# PCB_Project_TrafficLight.net
KiCad netlist of a schematic drawn in Altium Designer
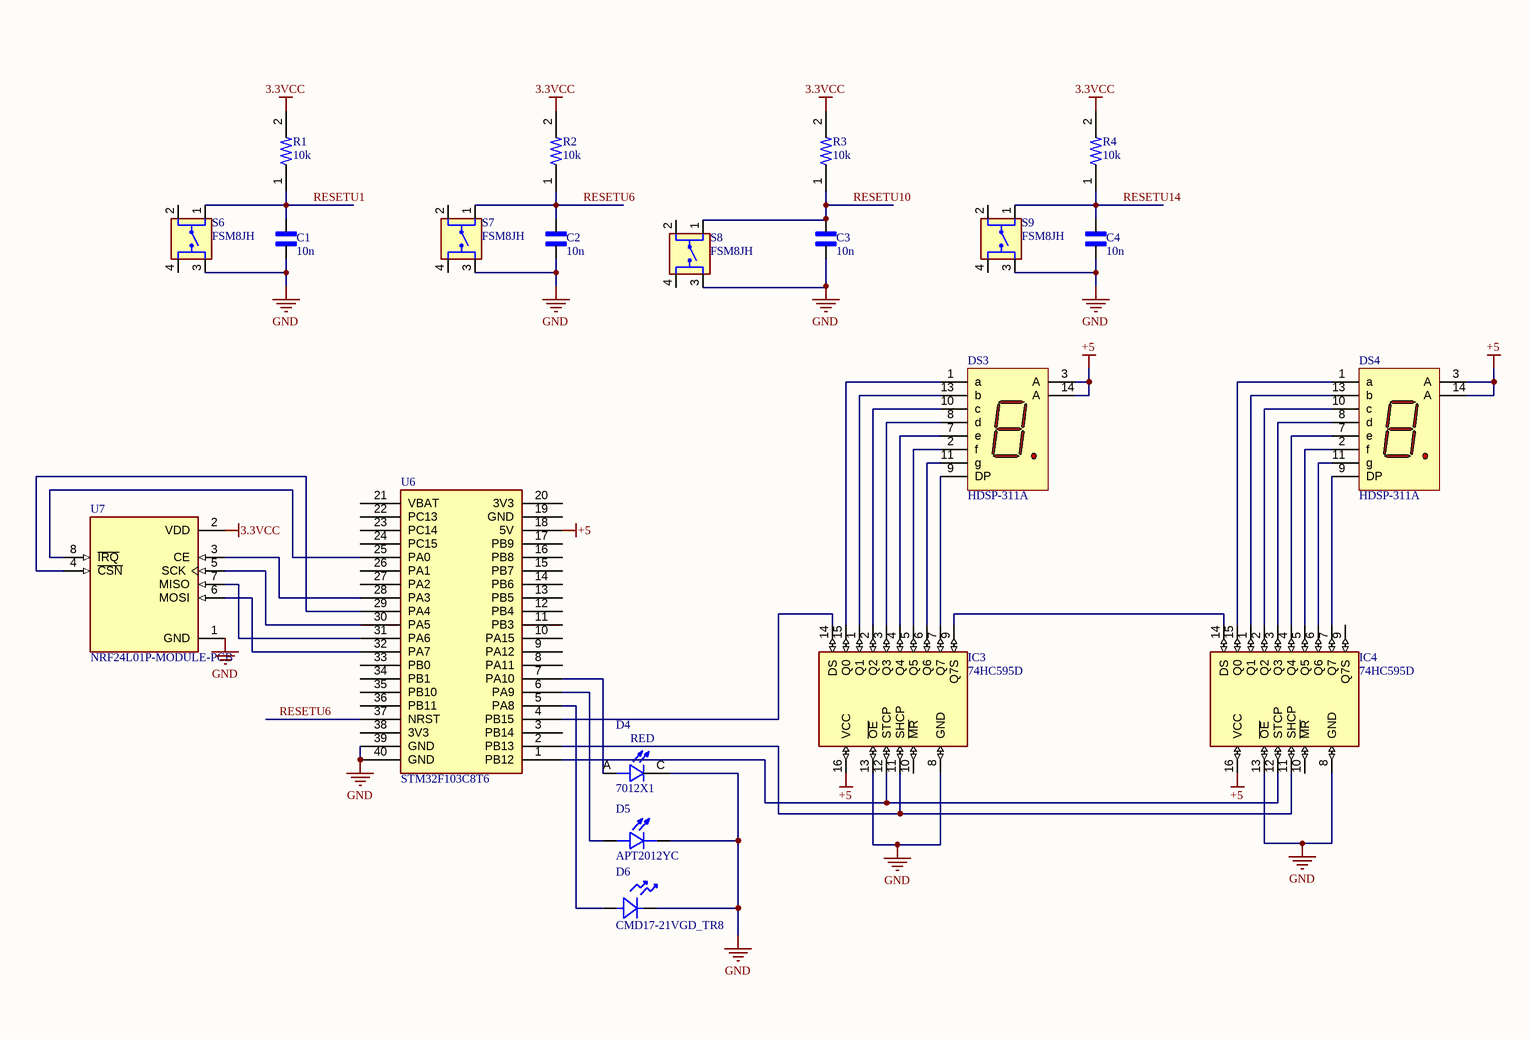
[diagram p0: PCB_Project_TrafficLight.SchDoc, left]
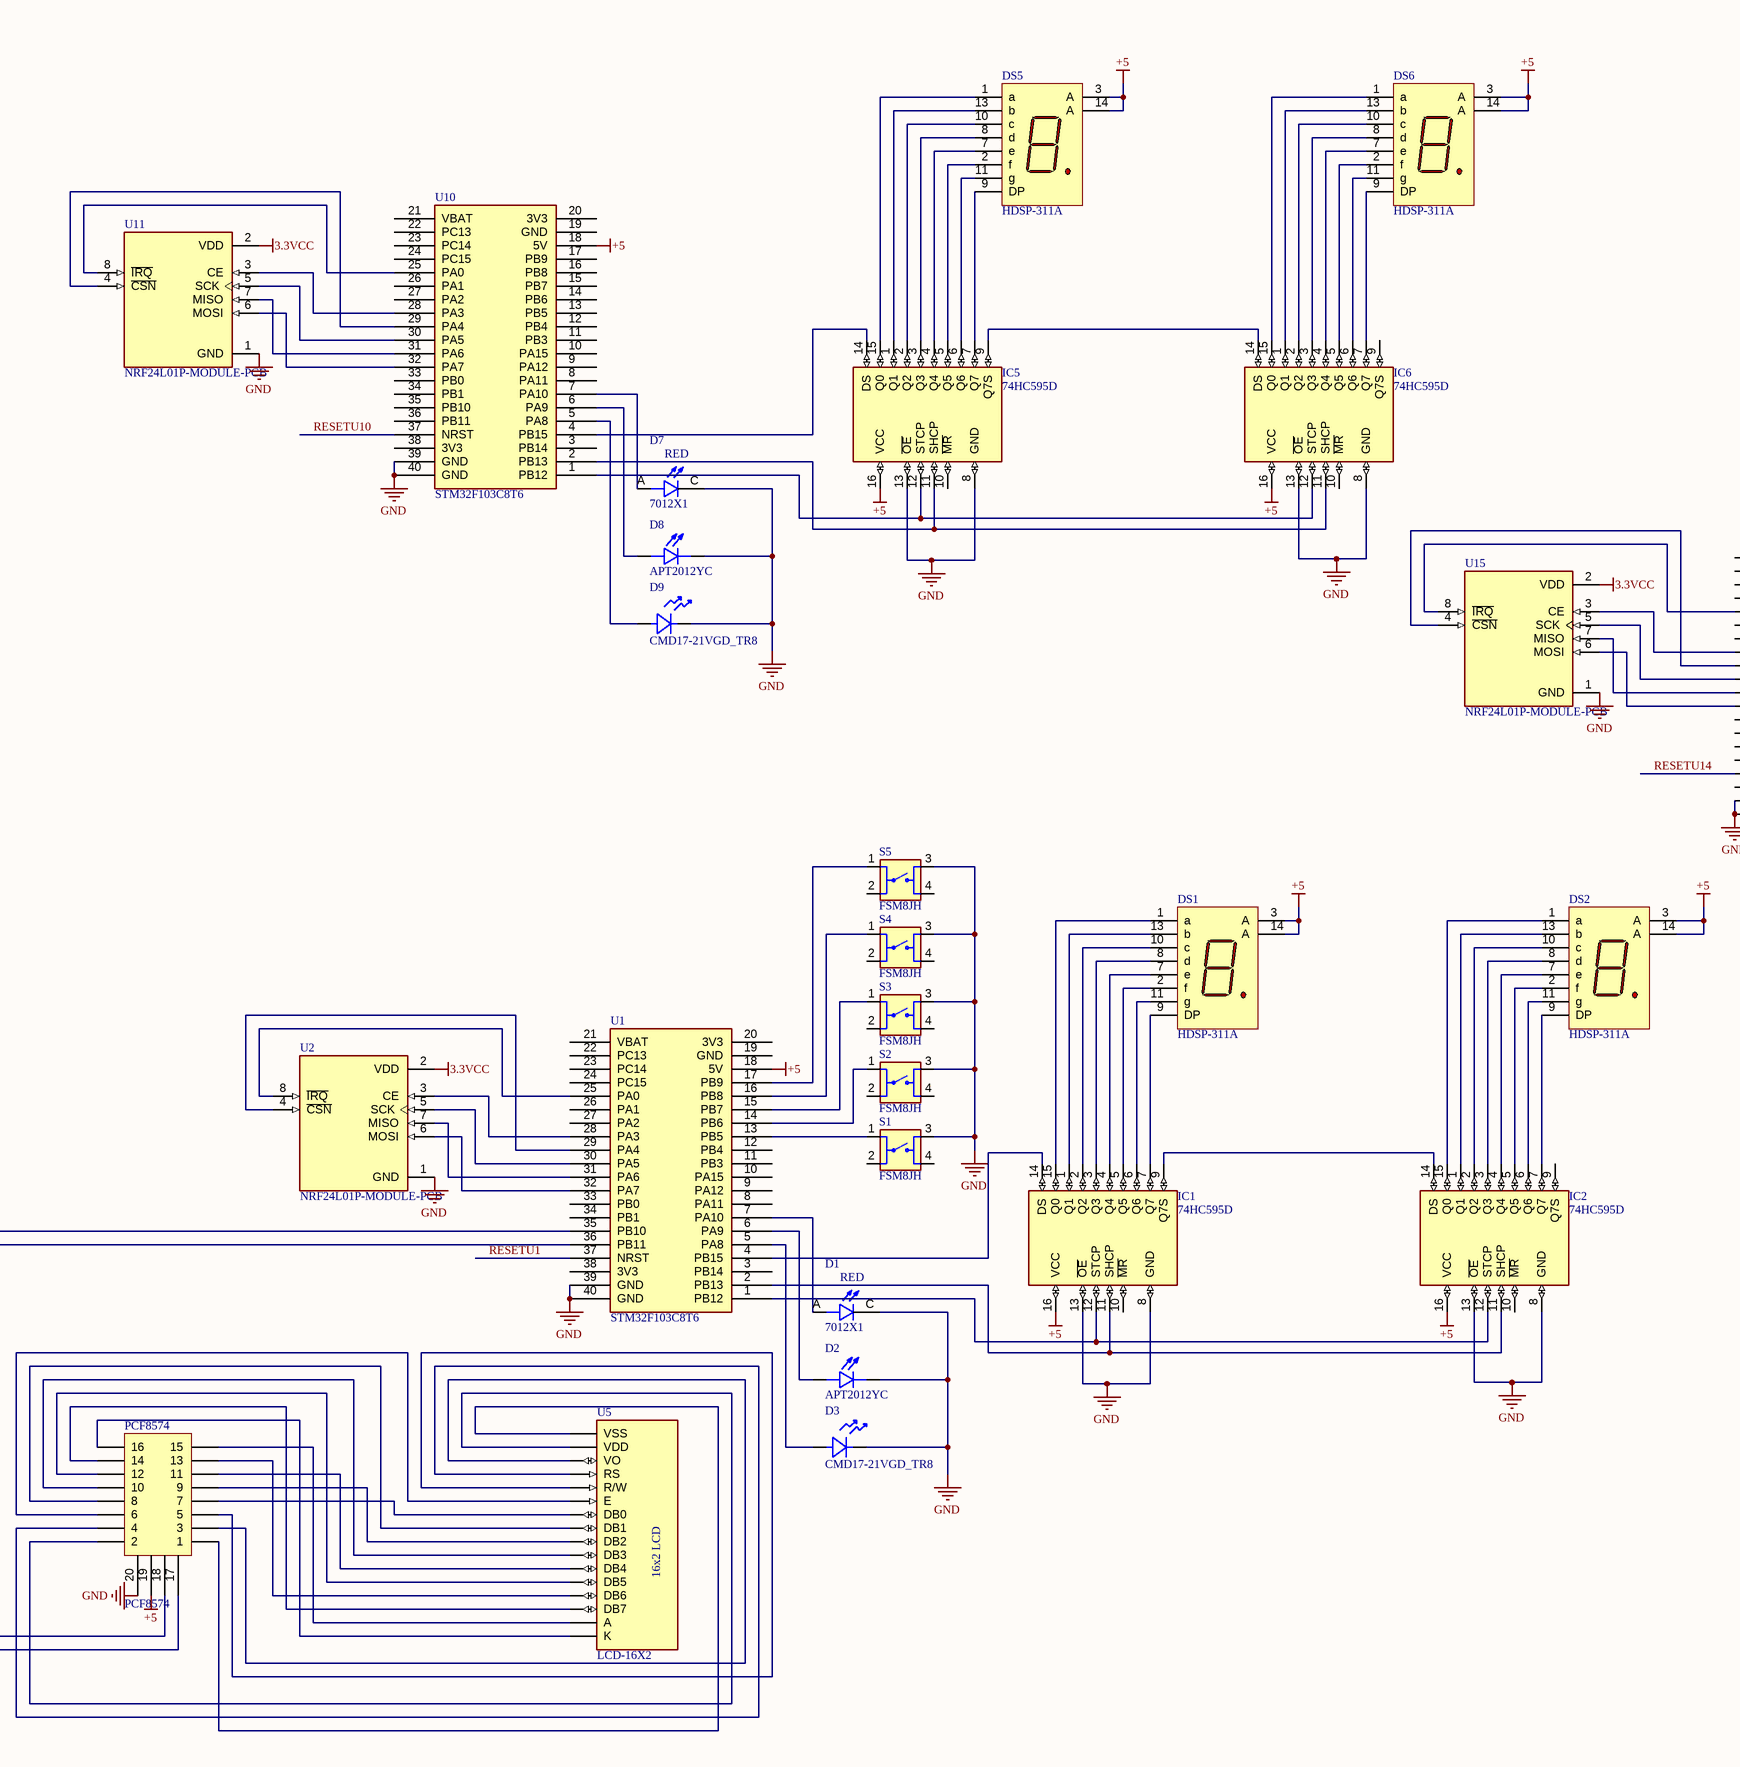
[diagram p1: PCB_Project_TrafficLight.SchDoc, middle]
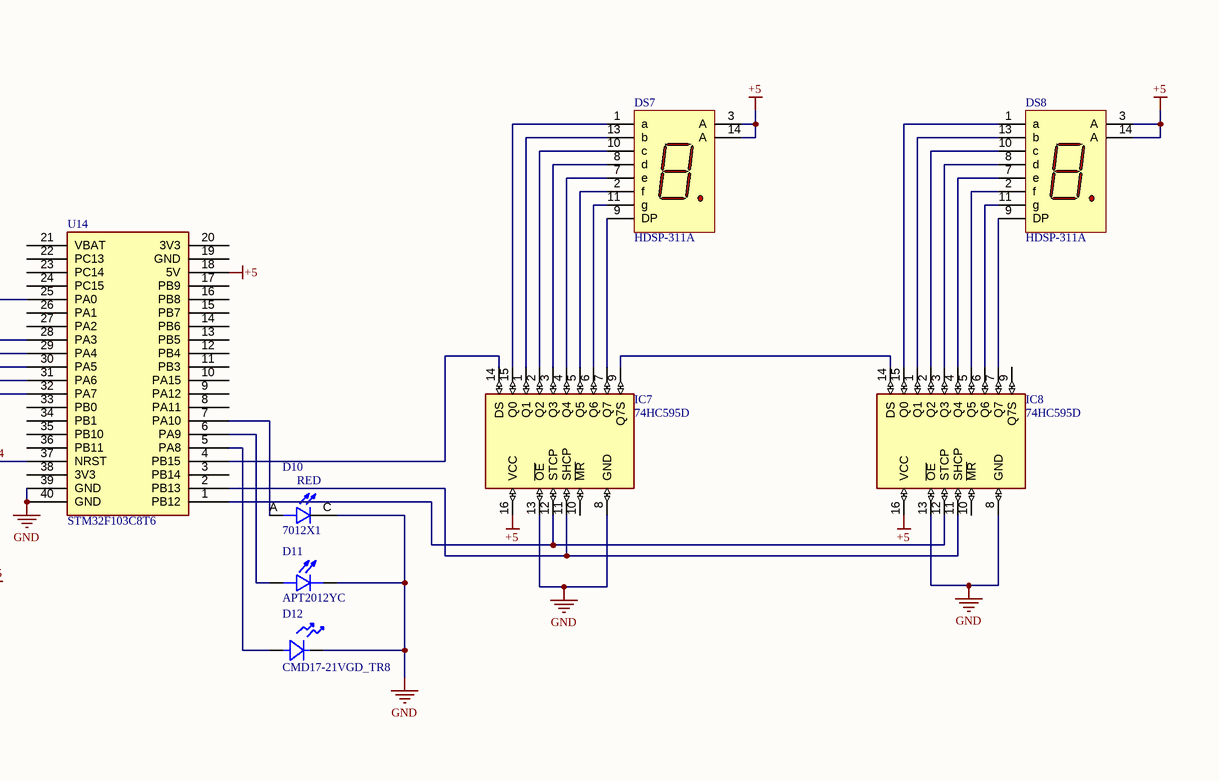
[diagram p2: PCB_Project_TrafficLight.SchDoc, right]

(export (version "E")
  (design (tool "Eeschema 10.0.6"))
  (components
    (comp (ref "C1")
      (value "10n")
      (footprint "CAPC1005X55N")
      (description "Multilayer Ceramic Capacitors MLCC - SMD/SMT")
      (fields (field (name "MF") "Murata") (field (name "MP") "GCM155R11H103KA40D"))
      (libsource (lib "GCM155R11H103KA40D") (part "GCM155R11H103KA40D"))
    )
    (comp (ref "C2")
      (value "10n")
      (footprint "CAPC1005X55N")
      (description "Multilayer Ceramic Capacitors MLCC - SMD/SMT")
      (fields (field (name "MF") "Murata") (field (name "MP") "GCM155R11H103KA40D"))
      (libsource (lib "GCM155R11H103KA40D") (part "GCM155R11H103KA40D"))
    )
    (comp (ref "C3")
      (value "10n")
      (footprint "CAPC1005X55N")
      (description "Multilayer Ceramic Capacitors MLCC - SMD/SMT")
      (fields (field (name "MF") "Murata") (field (name "MP") "GCM155R11H103KA40D"))
      (libsource (lib "GCM155R11H103KA40D") (part "GCM155R11H103KA40D"))
    )
    (comp (ref "C4")
      (value "10n")
      (footprint "CAPC1005X55N")
      (description "Multilayer Ceramic Capacitors MLCC - SMD/SMT")
      (fields (field (name "MF") "Murata") (field (name "MP") "GCM155R11H103KA40D"))
      (libsource (lib "GCM155R11H103KA40D") (part "GCM155R11H103KA40D"))
    )
    (comp (ref "D1")
      (value "7012X1")
      (footprint "LED_7012X1")
      (description "Red - LED Indication - Discrete 1.7V 0805 (2012 Metric)")
      (fields (field (name "MF") "VCC"))
      (libsource (lib "7012X1") (part "7012X1"))
    )
    (comp (ref "D2")
      (value "APT2012YC")
      (footprint "LED_APT2012YC")
      (fields (field (name "MF") "{'manufacturer': u'Kingbright'}"))
      (libsource (lib "APT2012YC") (part "APT2012YC"))
    )
    (comp (ref "D3")
      (value "CMD17-21VGD_TR8")
      (footprint "LED_CMD17-21VGD_TR8")
      (description "Green - LED Indication - Discrete 2.1V 0805 (2012 Metric)")
      (fields (field (name "MF") "VCC") (field (name "MP") "CMD17-21VGD/TR8"))
      (libsource (lib "CMD17-21VGD_TR8") (part "CMD17-21VGD_TR8"))
    )
    (comp (ref "D4")
      (value "7012X1")
      (footprint "LED_7012X1")
      (description "Red - LED Indication - Discrete 1.7V 0805 (2012 Metric)")
      (fields (field (name "MF") "VCC"))
      (libsource (lib "7012X1") (part "7012X1"))
    )
    (comp (ref "D5")
      (value "APT2012YC")
      (footprint "LED_APT2012YC")
      (fields (field (name "MF") "{'manufacturer': u'Kingbright'}"))
      (libsource (lib "APT2012YC") (part "APT2012YC"))
    )
    (comp (ref "D6")
      (value "CMD17-21VGD_TR8")
      (footprint "LED_CMD17-21VGD_TR8")
      (description "Green - LED Indication - Discrete 2.1V 0805 (2012 Metric)")
      (fields (field (name "MF") "VCC") (field (name "MP") "CMD17-21VGD/TR8"))
      (libsource (lib "CMD17-21VGD_TR8") (part "CMD17-21VGD_TR8"))
    )
    (comp (ref "D7")
      (value "7012X1")
      (footprint "LED_7012X1")
      (description "Red - LED Indication - Discrete 1.7V 0805 (2012 Metric)")
      (fields (field (name "MF") "VCC"))
      (libsource (lib "7012X1") (part "7012X1"))
    )
    (comp (ref "D8")
      (value "APT2012YC")
      (footprint "LED_APT2012YC")
      (fields (field (name "MF") "{'manufacturer': u'Kingbright'}"))
      (libsource (lib "APT2012YC") (part "APT2012YC"))
    )
    (comp (ref "D9")
      (value "CMD17-21VGD_TR8")
      (footprint "LED_CMD17-21VGD_TR8")
      (description "Green - LED Indication - Discrete 2.1V 0805 (2012 Metric)")
      (fields (field (name "MF") "VCC") (field (name "MP") "CMD17-21VGD/TR8"))
      (libsource (lib "CMD17-21VGD_TR8") (part "CMD17-21VGD_TR8"))
    )
    (comp (ref "D10")
      (value "7012X1")
      (footprint "LED_7012X1")
      (description "Red - LED Indication - Discrete 1.7V 0805 (2012 Metric)")
      (fields (field (name "MF") "VCC"))
      (libsource (lib "7012X1") (part "7012X1"))
    )
    (comp (ref "D11")
      (value "APT2012YC")
      (footprint "LED_APT2012YC")
      (fields (field (name "MF") "{'manufacturer': u'Kingbright'}"))
      (libsource (lib "APT2012YC") (part "APT2012YC"))
    )
    (comp (ref "D12")
      (value "CMD17-21VGD_TR8")
      (footprint "LED_CMD17-21VGD_TR8")
      (description "Green - LED Indication - Discrete 2.1V 0805 (2012 Metric)")
      (fields (field (name "MF") "VCC") (field (name "MP") "CMD17-21VGD/TR8"))
      (libsource (lib "CMD17-21VGD_TR8") (part "CMD17-21VGD_TR8"))
    )
    (comp (ref "DS1")
      (value "HDSP-311A")
      (footprint "F-10(14)")
      (description "10.16 mm Single Digit General Purpose AlGaAs Red 7-Segment Display: CA, RH DP")
      (fields (field (name "PUBLISHER") "Altium Limited"))
      (libsource (lib "Agilent LED Display 7-Segment, 1-Digit") (part "HDSP-311A"))
    )
    (comp (ref "DS2")
      (value "HDSP-311A")
      (footprint "F-10(14)")
      (description "10.16 mm Single Digit General Purpose AlGaAs Red 7-Segment Display: CA, RH DP")
      (fields (field (name "PUBLISHER") "Altium Limited"))
      (libsource (lib "Agilent LED Display 7-Segment, 1-Digit") (part "HDSP-311A"))
    )
    (comp (ref "DS3")
      (value "HDSP-311A")
      (footprint "F-10(14)")
      (description "10.16 mm Single Digit General Purpose AlGaAs Red 7-Segment Display: CA, RH DP")
      (fields (field (name "PUBLISHER") "Altium Limited"))
      (libsource (lib "Agilent LED Display 7-Segment, 1-Digit") (part "HDSP-311A"))
    )
    (comp (ref "DS4")
      (value "HDSP-311A")
      (footprint "F-10(14)")
      (description "10.16 mm Single Digit General Purpose AlGaAs Red 7-Segment Display: CA, RH DP")
      (fields (field (name "PUBLISHER") "Altium Limited"))
      (libsource (lib "Agilent LED Display 7-Segment, 1-Digit") (part "HDSP-311A"))
    )
    (comp (ref "DS5")
      (value "HDSP-311A")
      (footprint "F-10(14)")
      (description "10.16 mm Single Digit General Purpose AlGaAs Red 7-Segment Display: CA, RH DP")
      (fields (field (name "PUBLISHER") "Altium Limited"))
      (libsource (lib "Agilent LED Display 7-Segment, 1-Digit") (part "HDSP-311A"))
    )
    (comp (ref "DS6")
      (value "HDSP-311A")
      (footprint "F-10(14)")
      (description "10.16 mm Single Digit General Purpose AlGaAs Red 7-Segment Display: CA, RH DP")
      (fields (field (name "PUBLISHER") "Altium Limited"))
      (libsource (lib "Agilent LED Display 7-Segment, 1-Digit") (part "HDSP-311A"))
    )
    (comp (ref "DS7")
      (value "HDSP-311A")
      (footprint "F-10(14)")
      (description "10.16 mm Single Digit General Purpose AlGaAs Red 7-Segment Display: CA, RH DP")
      (fields (field (name "PUBLISHER") "Altium Limited"))
      (libsource (lib "Agilent LED Display 7-Segment, 1-Digit") (part "HDSP-311A"))
    )
    (comp (ref "DS8")
      (value "HDSP-311A")
      (footprint "F-10(14)")
      (description "10.16 mm Single Digit General Purpose AlGaAs Red 7-Segment Display: CA, RH DP")
      (fields (field (name "PUBLISHER") "Altium Limited"))
      (libsource (lib "Agilent LED Display 7-Segment, 1-Digit") (part "HDSP-311A"))
    )
    (comp (ref "IC1")
      (value "74HC595D")
      (footprint "SOIC127P600X175-16N")
      (description "Shift Register Single 8-Bit Serial to Serial/Parallel 16-Pin SOIC T/R")
      (fields (field (name "MF") "NXP Semiconductors"))
      (libsource (lib "74HC595D") (part "74HC595D"))
    )
    (comp (ref "IC2")
      (value "74HC595D")
      (footprint "SOIC127P600X175-16N")
      (description "Shift Register Single 8-Bit Serial to Serial/Parallel 16-Pin SOIC T/R")
      (fields (field (name "MF") "NXP Semiconductors"))
      (libsource (lib "74HC595D") (part "74HC595D"))
    )
    (comp (ref "IC3")
      (value "74HC595D")
      (footprint "SOIC127P600X175-16N")
      (description "Shift Register Single 8-Bit Serial to Serial/Parallel 16-Pin SOIC T/R")
      (fields (field (name "MF") "NXP Semiconductors"))
      (libsource (lib "74HC595D") (part "74HC595D"))
    )
    (comp (ref "IC4")
      (value "74HC595D")
      (footprint "SOIC127P600X175-16N")
      (description "Shift Register Single 8-Bit Serial to Serial/Parallel 16-Pin SOIC T/R")
      (fields (field (name "MF") "NXP Semiconductors"))
      (libsource (lib "74HC595D") (part "74HC595D"))
    )
    (comp (ref "IC5")
      (value "74HC595D")
      (footprint "SOIC127P600X175-16N")
      (description "Shift Register Single 8-Bit Serial to Serial/Parallel 16-Pin SOIC T/R")
      (fields (field (name "MF") "NXP Semiconductors"))
      (libsource (lib "74HC595D") (part "74HC595D"))
    )
    (comp (ref "IC6")
      (value "74HC595D")
      (footprint "SOIC127P600X175-16N")
      (description "Shift Register Single 8-Bit Serial to Serial/Parallel 16-Pin SOIC T/R")
      (fields (field (name "MF") "NXP Semiconductors"))
      (libsource (lib "74HC595D") (part "74HC595D"))
    )
    (comp (ref "IC7")
      (value "74HC595D")
      (footprint "SOIC127P600X175-16N")
      (description "Shift Register Single 8-Bit Serial to Serial/Parallel 16-Pin SOIC T/R")
      (fields (field (name "MF") "NXP Semiconductors"))
      (libsource (lib "74HC595D") (part "74HC595D"))
    )
    (comp (ref "IC8")
      (value "74HC595D")
      (footprint "SOIC127P600X175-16N")
      (description "Shift Register Single 8-Bit Serial to Serial/Parallel 16-Pin SOIC T/R")
      (fields (field (name "MF") "NXP Semiconductors"))
      (libsource (lib "74HC595D") (part "74HC595D"))
    )
    (comp (ref "PCF8574")
      (value "PCF8574")
      (footprint "PCF8574")
      (libsource (lib "PCF8574") (part "PCF8574"))
    )
    (comp (ref "R1")
      (value "10k")
      (footprint "RESC1608X50N_CPF0603F10KC1")
      (description "Res Thin Film 0603 10K Ohm 1% 1/16W Â±50ppm/Â°C Molded SMD SMD Paper T/R")
      (fields (field (name "TOLERANCE") "1%") (field (name "MF") "TE Connectivity"))
      (libsource (lib "CPF0603F10KC1") (part "CPF0603F10KC1"))
    )
    (comp (ref "R2")
      (value "10k")
      (footprint "RESC1608X50N_CPF0603F10KC1")
      (description "Res Thin Film 0603 10K Ohm 1% 1/16W Â±50ppm/Â°C Molded SMD SMD Paper T/R")
      (fields (field (name "TOLERANCE") "1%") (field (name "MF") "TE Connectivity"))
      (libsource (lib "CPF0603F10KC1") (part "CPF0603F10KC1"))
    )
    (comp (ref "R3")
      (value "10k")
      (footprint "RESC1608X50N_CPF0603F10KC1")
      (description "Res Thin Film 0603 10K Ohm 1% 1/16W Â±50ppm/Â°C Molded SMD SMD Paper T/R")
      (fields (field (name "TOLERANCE") "1%") (field (name "MF") "TE Connectivity"))
      (libsource (lib "CPF0603F10KC1") (part "CPF0603F10KC1"))
    )
    (comp (ref "R4")
      (value "10k")
      (footprint "RESC1608X50N_CPF0603F10KC1")
      (description "Res Thin Film 0603 10K Ohm 1% 1/16W Â±50ppm/Â°C Molded SMD SMD Paper T/R")
      (fields (field (name "TOLERANCE") "1%") (field (name "MF") "TE Connectivity"))
      (libsource (lib "CPF0603F10KC1") (part "CPF0603F10KC1"))
    )
    (comp (ref "S1")
      (value "FSM8JH")
      (footprint "SW_FSM8JH")
      (description "Tactile Switch SPST-NO Top Actuated Through Hole")
      (fields (field (name "MF") "TE Connectivity"))
      (libsource (lib "") (part "FSM8JH_1"))
    )
    (comp (ref "S2")
      (value "FSM8JH")
      (footprint "SW_FSM8JH")
      (description "Tactile Switch SPST-NO Top Actuated Through Hole")
      (fields (field (name "MF") "TE Connectivity"))
      (libsource (lib "") (part "FSM8JH_1"))
    )
    (comp (ref "S3")
      (value "FSM8JH")
      (footprint "SW_FSM8JH")
      (description "Tactile Switch SPST-NO Top Actuated Through Hole")
      (fields (field (name "MF") "TE Connectivity"))
      (libsource (lib "") (part "FSM8JH_1"))
    )
    (comp (ref "S4")
      (value "FSM8JH")
      (footprint "SW_FSM8JH")
      (description "Tactile Switch SPST-NO Top Actuated Through Hole")
      (fields (field (name "MF") "TE Connectivity"))
      (libsource (lib "") (part "FSM8JH_1"))
    )
    (comp (ref "S5")
      (value "FSM8JH")
      (footprint "SW_FSM8JH")
      (description "Tactile Switch SPST-NO Top Actuated Through Hole")
      (fields (field (name "MF") "TE Connectivity"))
      (libsource (lib "") (part "FSM8JH_1"))
    )
    (comp (ref "S6")
      (value "FSM8JH")
      (footprint "SW_FSM8JH")
      (description "Tactile Switch SPST-NO Top Actuated Through Hole")
      (fields (field (name "MF") "TE Connectivity"))
      (libsource (lib "FSM8JH") (part "FSM8JH"))
    )
    (comp (ref "S7")
      (value "FSM8JH")
      (footprint "SW_FSM8JH")
      (description "Tactile Switch SPST-NO Top Actuated Through Hole")
      (fields (field (name "MF") "TE Connectivity"))
      (libsource (lib "FSM8JH") (part "FSM8JH"))
    )
    (comp (ref "S8")
      (value "FSM8JH")
      (footprint "SW_FSM8JH")
      (description "Tactile Switch SPST-NO Top Actuated Through Hole")
      (fields (field (name "MF") "TE Connectivity"))
      (libsource (lib "FSM8JH") (part "FSM8JH"))
    )
    (comp (ref "S9")
      (value "FSM8JH")
      (footprint "SW_FSM8JH")
      (description "Tactile Switch SPST-NO Top Actuated Through Hole")
      (fields (field (name "MF") "TE Connectivity"))
      (libsource (lib "FSM8JH") (part "FSM8JH"))
    )
    (comp (ref "U1")
      (value "STM32F103C8T6")
      (footprint "Stm32 BluePill")
      (description "Designed By @Alixahedi")
      (libsource (lib "Stm32 Blue Pill") (part "BluePill"))
    )
    (comp (ref "U2")
      (value "NRF24L01P-MODULE-PCB")
      (footprint "XCVR_NRF24L01P-MODULE-PCB")
      (description "- Transceiver For Use With nRF24L01+")
      (fields (field (name "MF") "Nordic Semiconductor"))
      (libsource (lib "NRF24L01P-MODULE-PCB") (part "NRF24L01P-MODULE-PCB"))
    )
    (comp (ref "U5")
      (value "LCD-16X2")
      (footprint "MODULE_LCD-16X2")
      (description "Display Development Tools 16x2 Black on Green Char LCD w Backlight")
      (fields (field (name "MF") "Gravitech"))
      (libsource (lib "LCD-16X2") (part "LCD-16X2"))
    )
    (comp (ref "U6")
      (value "STM32F103C8T6")
      (footprint "Stm32 BluePill")
      (description "Designed By @Alixahedi")
      (libsource (lib "Stm32 Blue Pill") (part "BluePill"))
    )
    (comp (ref "U7")
      (value "NRF24L01P-MODULE-PCB")
      (footprint "XCVR_NRF24L01P-MODULE-PCB")
      (description "- Transceiver For Use With nRF24L01+")
      (fields (field (name "MF") "Nordic Semiconductor"))
      (libsource (lib "NRF24L01P-MODULE-PCB") (part "NRF24L01P-MODULE-PCB"))
    )
    (comp (ref "U10")
      (value "STM32F103C8T6")
      (footprint "Stm32 BluePill")
      (description "Designed By @Alixahedi")
      (libsource (lib "Stm32 Blue Pill") (part "BluePill"))
    )
    (comp (ref "U11")
      (value "NRF24L01P-MODULE-PCB")
      (footprint "XCVR_NRF24L01P-MODULE-PCB")
      (description "- Transceiver For Use With nRF24L01+")
      (fields (field (name "MF") "Nordic Semiconductor"))
      (libsource (lib "NRF24L01P-MODULE-PCB") (part "NRF24L01P-MODULE-PCB"))
    )
    (comp (ref "U14")
      (value "STM32F103C8T6")
      (footprint "Stm32 BluePill")
      (description "Designed By @Alixahedi")
      (libsource (lib "Stm32 Blue Pill") (part "BluePill"))
    )
    (comp (ref "U15")
      (value "NRF24L01P-MODULE-PCB")
      (footprint "XCVR_NRF24L01P-MODULE-PCB")
      (description "- Transceiver For Use With nRF24L01+")
      (fields (field (name "MF") "Nordic Semiconductor"))
      (libsource (lib "NRF24L01P-MODULE-PCB") (part "NRF24L01P-MODULE-PCB"))
    )
  )
  (nets
    (net (code "1") (name "+5") (class "Default")
      (node (ref "DS1") (pin "14") (pinfunction "A_14") (pintype "passive"))
      (node (ref "DS1") (pin "3") (pinfunction "A_3") (pintype "passive"))
      (node (ref "DS2") (pin "14") (pinfunction "A_14") (pintype "passive"))
      (node (ref "DS2") (pin "3") (pinfunction "A_3") (pintype "passive"))
      (node (ref "DS3") (pin "14") (pinfunction "A_14") (pintype "passive"))
      (node (ref "DS3") (pin "3") (pinfunction "A_3") (pintype "passive"))
      (node (ref "DS4") (pin "14") (pinfunction "A_14") (pintype "passive"))
      (node (ref "DS4") (pin "3") (pinfunction "A_3") (pintype "passive"))
      (node (ref "DS5") (pin "14") (pinfunction "A_14") (pintype "passive"))
      (node (ref "DS5") (pin "3") (pinfunction "A_3") (pintype "passive"))
      (node (ref "DS6") (pin "14") (pinfunction "A_14") (pintype "passive"))
      (node (ref "DS6") (pin "3") (pinfunction "A_3") (pintype "passive"))
      (node (ref "DS7") (pin "14") (pinfunction "A_14") (pintype "passive"))
      (node (ref "DS7") (pin "3") (pinfunction "A_3") (pintype "passive"))
      (node (ref "DS8") (pin "14") (pinfunction "A_14") (pintype "passive"))
      (node (ref "DS8") (pin "3") (pinfunction "A_3") (pintype "passive"))
      (node (ref "IC1") (pin "16") (pinfunction "VCC_16") (pintype "bidirectional"))
      (node (ref "IC2") (pin "16") (pinfunction "VCC_16") (pintype "bidirectional"))
      (node (ref "IC3") (pin "16") (pinfunction "VCC_16") (pintype "bidirectional"))
      (node (ref "IC4") (pin "16") (pinfunction "VCC_16") (pintype "bidirectional"))
      (node (ref "IC5") (pin "16") (pinfunction "VCC_16") (pintype "bidirectional"))
      (node (ref "IC6") (pin "16") (pinfunction "VCC_16") (pintype "bidirectional"))
      (node (ref "IC7") (pin "16") (pinfunction "VCC_16") (pintype "bidirectional"))
      (node (ref "IC8") (pin "16") (pinfunction "VCC_16") (pintype "bidirectional"))
      (node (ref "PCF8574") (pin "19") (pinfunction "19_19") (pintype "passive"))
      (node (ref "U1") (pin "18") (pinfunction "5V_18") (pintype "passive"))
      (node (ref "U10") (pin "18") (pinfunction "5V_18") (pintype "passive"))
      (node (ref "U14") (pin "18") (pinfunction "5V_18") (pintype "passive"))
      (node (ref "U6") (pin "18") (pinfunction "5V_18") (pintype "passive"))
    )
    (net (code "2") (name "/RESETU1") (class "Default")
      (node (ref "C1") (pin "2") (pinfunction "2_2") (pintype "passive"))
      (node (ref "R1") (pin "1") (pinfunction "1_1") (pintype "passive"))
      (node (ref "S6") (pin "1") (pinfunction "1_1") (pintype "passive"))
      (node (ref "U1") (pin "37") (pinfunction "NRST_37") (pintype "passive"))
    )
    (net (code "3") (name "/RESETU6") (class "Default")
      (node (ref "C2") (pin "2") (pinfunction "2_2") (pintype "passive"))
      (node (ref "R2") (pin "1") (pinfunction "1_1") (pintype "passive"))
      (node (ref "S7") (pin "1") (pinfunction "1_1") (pintype "passive"))
      (node (ref "U6") (pin "37") (pinfunction "NRST_37") (pintype "passive"))
    )
    (net (code "4") (name "/RESETU10") (class "Default")
      (node (ref "C3") (pin "2") (pinfunction "2_2") (pintype "passive"))
      (node (ref "R3") (pin "1") (pinfunction "1_1") (pintype "passive"))
      (node (ref "S8") (pin "1") (pinfunction "1_1") (pintype "passive"))
      (node (ref "U10") (pin "37") (pinfunction "NRST_37") (pintype "passive"))
    )
    (net (code "5") (name "/RESETU14") (class "Default")
      (node (ref "C4") (pin "2") (pinfunction "2_2") (pintype "passive"))
      (node (ref "R4") (pin "1") (pinfunction "1_1") (pintype "passive"))
      (node (ref "S9") (pin "1") (pinfunction "1_1") (pintype "passive"))
      (node (ref "U14") (pin "37") (pinfunction "NRST_37") (pintype "passive"))
    )
    (net (code "6") (name "3.3VCC") (class "Default")
      (node (ref "R1") (pin "2") (pinfunction "2_2") (pintype "passive"))
      (node (ref "R2") (pin "2") (pinfunction "2_2") (pintype "passive"))
      (node (ref "R3") (pin "2") (pinfunction "2_2") (pintype "passive"))
      (node (ref "R4") (pin "2") (pinfunction "2_2") (pintype "passive"))
      (node (ref "U11") (pin "2") (pinfunction "VDD_2") (pintype "power_in"))
      (node (ref "U15") (pin "2") (pinfunction "VDD_2") (pintype "power_in"))
      (node (ref "U2") (pin "2") (pinfunction "VDD_2") (pintype "power_in"))
      (node (ref "U7") (pin "2") (pinfunction "VDD_2") (pintype "power_in"))
    )
    (net (code "7") (name "GND") (class "Default")
      (node (ref "C1") (pin "1") (pinfunction "1_1") (pintype "passive"))
      (node (ref "C2") (pin "1") (pinfunction "1_1") (pintype "passive"))
      (node (ref "C3") (pin "1") (pinfunction "1_1") (pintype "passive"))
      (node (ref "C4") (pin "1") (pinfunction "1_1") (pintype "passive"))
      (node (ref "D1") (pin "C") (pinfunction "C_C") (pintype "passive"))
      (node (ref "D10") (pin "C") (pinfunction "C_C") (pintype "passive"))
      (node (ref "D11") (pin "1") (pinfunction "C_1") (pintype "passive"))
      (node (ref "D12") (pin "2") (pinfunction "2_2") (pintype "passive"))
      (node (ref "D2") (pin "1") (pinfunction "C_1") (pintype "passive"))
      (node (ref "D3") (pin "2") (pinfunction "2_2") (pintype "passive"))
      (node (ref "D4") (pin "C") (pinfunction "C_C") (pintype "passive"))
      (node (ref "D5") (pin "1") (pinfunction "C_1") (pintype "passive"))
      (node (ref "D6") (pin "2") (pinfunction "2_2") (pintype "passive"))
      (node (ref "D7") (pin "C") (pinfunction "C_C") (pintype "passive"))
      (node (ref "D8") (pin "1") (pinfunction "C_1") (pintype "passive"))
      (node (ref "D9") (pin "2") (pinfunction "2_2") (pintype "passive"))
      (node (ref "IC1") (pin "13") (pinfunction "~{OE}_13") (pintype "bidirectional"))
      (node (ref "IC1") (pin "8") (pinfunction "GND_8") (pintype "bidirectional"))
      (node (ref "IC2") (pin "13") (pinfunction "~{OE}_13") (pintype "bidirectional"))
      (node (ref "IC2") (pin "8") (pinfunction "GND_8") (pintype "bidirectional"))
      (node (ref "IC3") (pin "13") (pinfunction "~{OE}_13") (pintype "bidirectional"))
      (node (ref "IC3") (pin "8") (pinfunction "GND_8") (pintype "bidirectional"))
      (node (ref "IC4") (pin "13") (pinfunction "~{OE}_13") (pintype "bidirectional"))
      (node (ref "IC4") (pin "8") (pinfunction "GND_8") (pintype "bidirectional"))
      (node (ref "IC5") (pin "13") (pinfunction "~{OE}_13") (pintype "bidirectional"))
      (node (ref "IC5") (pin "8") (pinfunction "GND_8") (pintype "bidirectional"))
      (node (ref "IC6") (pin "13") (pinfunction "~{OE}_13") (pintype "bidirectional"))
      (node (ref "IC6") (pin "8") (pinfunction "GND_8") (pintype "bidirectional"))
      (node (ref "IC7") (pin "13") (pinfunction "~{OE}_13") (pintype "bidirectional"))
      (node (ref "IC7") (pin "8") (pinfunction "GND_8") (pintype "bidirectional"))
      (node (ref "IC8") (pin "13") (pinfunction "~{OE}_13") (pintype "bidirectional"))
      (node (ref "IC8") (pin "8") (pinfunction "GND_8") (pintype "bidirectional"))
      (node (ref "PCF8574") (pin "20") (pinfunction "20_20") (pintype "passive"))
      (node (ref "S1") (pin "3") (pinfunction "3_3") (pintype "passive"))
      (node (ref "S2") (pin "3") (pinfunction "3_3") (pintype "passive"))
      (node (ref "S3") (pin "3") (pinfunction "3_3") (pintype "passive"))
      (node (ref "S4") (pin "3") (pinfunction "3_3") (pintype "passive"))
      (node (ref "S5") (pin "3") (pinfunction "3_3") (pintype "passive"))
      (node (ref "S6") (pin "3") (pinfunction "3_3") (pintype "passive"))
      (node (ref "S7") (pin "3") (pinfunction "3_3") (pintype "passive"))
      (node (ref "S8") (pin "3") (pinfunction "3_3") (pintype "passive"))
      (node (ref "S9") (pin "3") (pinfunction "3_3") (pintype "passive"))
      (node (ref "U1") (pin "39") (pinfunction "GND_39") (pintype "passive"))
      (node (ref "U1") (pin "40") (pinfunction "GND_40") (pintype "passive"))
      (node (ref "U10") (pin "39") (pinfunction "GND_39") (pintype "passive"))
      (node (ref "U10") (pin "40") (pinfunction "GND_40") (pintype "passive"))
      (node (ref "U11") (pin "1") (pinfunction "GND_1") (pintype "power_in"))
      (node (ref "U14") (pin "39") (pinfunction "GND_39") (pintype "passive"))
      (node (ref "U14") (pin "40") (pinfunction "GND_40") (pintype "passive"))
      (node (ref "U15") (pin "1") (pinfunction "GND_1") (pintype "power_in"))
      (node (ref "U2") (pin "1") (pinfunction "GND_1") (pintype "power_in"))
      (node (ref "U6") (pin "39") (pinfunction "GND_39") (pintype "passive"))
      (node (ref "U6") (pin "40") (pinfunction "GND_40") (pintype "passive"))
      (node (ref "U7") (pin "1") (pinfunction "GND_1") (pintype "power_in"))
    )
    (net (code "8") (name "Net-(D2-A)") (class "Default")
      (node (ref "D2") (pin "2") (pinfunction "A_2") (pintype "passive"))
      (node (ref "U1") (pin "6") (pinfunction "PA9_6") (pintype "passive"))
    )
    (net (code "9") (name "Net-(D5-A)") (class "Default")
      (node (ref "D5") (pin "2") (pinfunction "A_2") (pintype "passive"))
      (node (ref "U6") (pin "6") (pinfunction "PA9_6") (pintype "passive"))
    )
    (net (code "10") (name "Net-(D8-A)") (class "Default")
      (node (ref "D8") (pin "2") (pinfunction "A_2") (pintype "passive"))
      (node (ref "U10") (pin "6") (pinfunction "PA9_6") (pintype "passive"))
    )
    (net (code "11") (name "Net-(D11-A)") (class "Default")
      (node (ref "D11") (pin "2") (pinfunction "A_2") (pintype "passive"))
      (node (ref "U14") (pin "6") (pinfunction "PA9_6") (pintype "passive"))
    )
    (net (code "12") (name "Net-(DS1-DP)") (class "Default")
      (node (ref "DS1") (pin "9") (pinfunction "DP_9") (pintype "passive"))
      (node (ref "IC1") (pin "7") (pinfunction "Q7_7") (pintype "bidirectional"))
    )
    (net (code "13") (name "Net-(DS1-a)") (class "Default")
      (node (ref "DS1") (pin "1") (pinfunction "a_1") (pintype "passive"))
      (node (ref "IC1") (pin "15") (pinfunction "Q0_15") (pintype "bidirectional"))
    )
    (net (code "14") (name "Net-(DS1-b)") (class "Default")
      (node (ref "DS1") (pin "13") (pinfunction "b_13") (pintype "passive"))
      (node (ref "IC1") (pin "1") (pinfunction "Q1_1") (pintype "bidirectional"))
    )
    (net (code "15") (name "Net-(DS1-c)") (class "Default")
      (node (ref "DS1") (pin "10") (pinfunction "c_10") (pintype "passive"))
      (node (ref "IC1") (pin "2") (pinfunction "Q2_2") (pintype "bidirectional"))
    )
    (net (code "16") (name "Net-(DS1-d)") (class "Default")
      (node (ref "DS1") (pin "8") (pinfunction "d_8") (pintype "passive"))
      (node (ref "IC1") (pin "3") (pinfunction "Q3_3") (pintype "bidirectional"))
    )
    (net (code "17") (name "Net-(DS1-e)") (class "Default")
      (node (ref "DS1") (pin "7") (pinfunction "e_7") (pintype "passive"))
      (node (ref "IC1") (pin "4") (pinfunction "Q4_4") (pintype "bidirectional"))
    )
    (net (code "18") (name "Net-(DS1-f)") (class "Default")
      (node (ref "DS1") (pin "2") (pinfunction "f_2") (pintype "passive"))
      (node (ref "IC1") (pin "5") (pinfunction "Q5_5") (pintype "bidirectional"))
    )
    (net (code "19") (name "Net-(DS1-g)") (class "Default")
      (node (ref "DS1") (pin "11") (pinfunction "g_11") (pintype "passive"))
      (node (ref "IC1") (pin "6") (pinfunction "Q6_6") (pintype "bidirectional"))
    )
    (net (code "20") (name "Net-(DS2-DP)") (class "Default")
      (node (ref "DS2") (pin "9") (pinfunction "DP_9") (pintype "passive"))
      (node (ref "IC2") (pin "7") (pinfunction "Q7_7") (pintype "bidirectional"))
    )
    (net (code "21") (name "Net-(DS2-a)") (class "Default")
      (node (ref "DS2") (pin "1") (pinfunction "a_1") (pintype "passive"))
      (node (ref "IC2") (pin "15") (pinfunction "Q0_15") (pintype "bidirectional"))
    )
    (net (code "22") (name "Net-(DS2-b)") (class "Default")
      (node (ref "DS2") (pin "13") (pinfunction "b_13") (pintype "passive"))
      (node (ref "IC2") (pin "1") (pinfunction "Q1_1") (pintype "bidirectional"))
    )
    (net (code "23") (name "Net-(DS2-c)") (class "Default")
      (node (ref "DS2") (pin "10") (pinfunction "c_10") (pintype "passive"))
      (node (ref "IC2") (pin "2") (pinfunction "Q2_2") (pintype "bidirectional"))
    )
    (net (code "24") (name "Net-(DS2-d)") (class "Default")
      (node (ref "DS2") (pin "8") (pinfunction "d_8") (pintype "passive"))
      (node (ref "IC2") (pin "3") (pinfunction "Q3_3") (pintype "bidirectional"))
    )
    (net (code "25") (name "Net-(DS2-e)") (class "Default")
      (node (ref "DS2") (pin "7") (pinfunction "e_7") (pintype "passive"))
      (node (ref "IC2") (pin "4") (pinfunction "Q4_4") (pintype "bidirectional"))
    )
    (net (code "26") (name "Net-(DS2-f)") (class "Default")
      (node (ref "DS2") (pin "2") (pinfunction "f_2") (pintype "passive"))
      (node (ref "IC2") (pin "5") (pinfunction "Q5_5") (pintype "bidirectional"))
    )
    (net (code "27") (name "Net-(DS2-g)") (class "Default")
      (node (ref "DS2") (pin "11") (pinfunction "g_11") (pintype "passive"))
      (node (ref "IC2") (pin "6") (pinfunction "Q6_6") (pintype "bidirectional"))
    )
    (net (code "28") (name "Net-(DS3-DP)") (class "Default")
      (node (ref "DS3") (pin "9") (pinfunction "DP_9") (pintype "passive"))
      (node (ref "IC3") (pin "7") (pinfunction "Q7_7") (pintype "bidirectional"))
    )
    (net (code "29") (name "Net-(DS3-a)") (class "Default")
      (node (ref "DS3") (pin "1") (pinfunction "a_1") (pintype "passive"))
      (node (ref "IC3") (pin "15") (pinfunction "Q0_15") (pintype "bidirectional"))
    )
    (net (code "30") (name "Net-(DS3-b)") (class "Default")
      (node (ref "DS3") (pin "13") (pinfunction "b_13") (pintype "passive"))
      (node (ref "IC3") (pin "1") (pinfunction "Q1_1") (pintype "bidirectional"))
    )
    (net (code "31") (name "Net-(DS3-c)") (class "Default")
      (node (ref "DS3") (pin "10") (pinfunction "c_10") (pintype "passive"))
      (node (ref "IC3") (pin "2") (pinfunction "Q2_2") (pintype "bidirectional"))
    )
    (net (code "32") (name "Net-(DS3-d)") (class "Default")
      (node (ref "DS3") (pin "8") (pinfunction "d_8") (pintype "passive"))
      (node (ref "IC3") (pin "3") (pinfunction "Q3_3") (pintype "bidirectional"))
    )
    (net (code "33") (name "Net-(DS3-e)") (class "Default")
      (node (ref "DS3") (pin "7") (pinfunction "e_7") (pintype "passive"))
      (node (ref "IC3") (pin "4") (pinfunction "Q4_4") (pintype "bidirectional"))
    )
    (net (code "34") (name "Net-(DS3-f)") (class "Default")
      (node (ref "DS3") (pin "2") (pinfunction "f_2") (pintype "passive"))
      (node (ref "IC3") (pin "5") (pinfunction "Q5_5") (pintype "bidirectional"))
    )
    (net (code "35") (name "Net-(DS3-g)") (class "Default")
      (node (ref "DS3") (pin "11") (pinfunction "g_11") (pintype "passive"))
      (node (ref "IC3") (pin "6") (pinfunction "Q6_6") (pintype "bidirectional"))
    )
    (net (code "36") (name "Net-(DS4-DP)") (class "Default")
      (node (ref "DS4") (pin "9") (pinfunction "DP_9") (pintype "passive"))
      (node (ref "IC4") (pin "7") (pinfunction "Q7_7") (pintype "bidirectional"))
    )
    (net (code "37") (name "Net-(DS4-a)") (class "Default")
      (node (ref "DS4") (pin "1") (pinfunction "a_1") (pintype "passive"))
      (node (ref "IC4") (pin "15") (pinfunction "Q0_15") (pintype "bidirectional"))
    )
    (net (code "38") (name "Net-(DS4-b)") (class "Default")
      (node (ref "DS4") (pin "13") (pinfunction "b_13") (pintype "passive"))
      (node (ref "IC4") (pin "1") (pinfunction "Q1_1") (pintype "bidirectional"))
    )
    (net (code "39") (name "Net-(DS4-c)") (class "Default")
      (node (ref "DS4") (pin "10") (pinfunction "c_10") (pintype "passive"))
      (node (ref "IC4") (pin "2") (pinfunction "Q2_2") (pintype "bidirectional"))
    )
    (net (code "40") (name "Net-(DS4-d)") (class "Default")
      (node (ref "DS4") (pin "8") (pinfunction "d_8") (pintype "passive"))
      (node (ref "IC4") (pin "3") (pinfunction "Q3_3") (pintype "bidirectional"))
    )
    (net (code "41") (name "Net-(DS4-e)") (class "Default")
      (node (ref "DS4") (pin "7") (pinfunction "e_7") (pintype "passive"))
      (node (ref "IC4") (pin "4") (pinfunction "Q4_4") (pintype "bidirectional"))
    )
    (net (code "42") (name "Net-(DS4-f)") (class "Default")
      (node (ref "DS4") (pin "2") (pinfunction "f_2") (pintype "passive"))
      (node (ref "IC4") (pin "5") (pinfunction "Q5_5") (pintype "bidirectional"))
    )
    (net (code "43") (name "Net-(DS4-g)") (class "Default")
      (node (ref "DS4") (pin "11") (pinfunction "g_11") (pintype "passive"))
      (node (ref "IC4") (pin "6") (pinfunction "Q6_6") (pintype "bidirectional"))
    )
    (net (code "44") (name "Net-(DS5-DP)") (class "Default")
      (node (ref "DS5") (pin "9") (pinfunction "DP_9") (pintype "passive"))
      (node (ref "IC5") (pin "7") (pinfunction "Q7_7") (pintype "bidirectional"))
    )
    (net (code "45") (name "Net-(DS5-a)") (class "Default")
      (node (ref "DS5") (pin "1") (pinfunction "a_1") (pintype "passive"))
      (node (ref "IC5") (pin "15") (pinfunction "Q0_15") (pintype "bidirectional"))
    )
    (net (code "46") (name "Net-(DS5-b)") (class "Default")
      (node (ref "DS5") (pin "13") (pinfunction "b_13") (pintype "passive"))
      (node (ref "IC5") (pin "1") (pinfunction "Q1_1") (pintype "bidirectional"))
    )
    (net (code "47") (name "Net-(DS5-c)") (class "Default")
      (node (ref "DS5") (pin "10") (pinfunction "c_10") (pintype "passive"))
      (node (ref "IC5") (pin "2") (pinfunction "Q2_2") (pintype "bidirectional"))
    )
    (net (code "48") (name "Net-(DS5-d)") (class "Default")
      (node (ref "DS5") (pin "8") (pinfunction "d_8") (pintype "passive"))
      (node (ref "IC5") (pin "3") (pinfunction "Q3_3") (pintype "bidirectional"))
    )
    (net (code "49") (name "Net-(DS5-e)") (class "Default")
      (node (ref "DS5") (pin "7") (pinfunction "e_7") (pintype "passive"))
      (node (ref "IC5") (pin "4") (pinfunction "Q4_4") (pintype "bidirectional"))
    )
    (net (code "50") (name "Net-(DS5-f)") (class "Default")
      (node (ref "DS5") (pin "2") (pinfunction "f_2") (pintype "passive"))
      (node (ref "IC5") (pin "5") (pinfunction "Q5_5") (pintype "bidirectional"))
    )
    (net (code "51") (name "Net-(DS5-g)") (class "Default")
      (node (ref "DS5") (pin "11") (pinfunction "g_11") (pintype "passive"))
      (node (ref "IC5") (pin "6") (pinfunction "Q6_6") (pintype "bidirectional"))
    )
    (net (code "52") (name "Net-(DS6-DP)") (class "Default")
      (node (ref "DS6") (pin "9") (pinfunction "DP_9") (pintype "passive"))
      (node (ref "IC6") (pin "7") (pinfunction "Q7_7") (pintype "bidirectional"))
    )
    (net (code "53") (name "Net-(DS6-a)") (class "Default")
      (node (ref "DS6") (pin "1") (pinfunction "a_1") (pintype "passive"))
      (node (ref "IC6") (pin "15") (pinfunction "Q0_15") (pintype "bidirectional"))
    )
    (net (code "54") (name "Net-(DS6-b)") (class "Default")
      (node (ref "DS6") (pin "13") (pinfunction "b_13") (pintype "passive"))
      (node (ref "IC6") (pin "1") (pinfunction "Q1_1") (pintype "bidirectional"))
    )
    (net (code "55") (name "Net-(DS6-c)") (class "Default")
      (node (ref "DS6") (pin "10") (pinfunction "c_10") (pintype "passive"))
      (node (ref "IC6") (pin "2") (pinfunction "Q2_2") (pintype "bidirectional"))
    )
    (net (code "56") (name "Net-(DS6-d)") (class "Default")
      (node (ref "DS6") (pin "8") (pinfunction "d_8") (pintype "passive"))
      (node (ref "IC6") (pin "3") (pinfunction "Q3_3") (pintype "bidirectional"))
    )
    (net (code "57") (name "Net-(DS6-e)") (class "Default")
      (node (ref "DS6") (pin "7") (pinfunction "e_7") (pintype "passive"))
      (node (ref "IC6") (pin "4") (pinfunction "Q4_4") (pintype "bidirectional"))
    )
    (net (code "58") (name "Net-(DS6-f)") (class "Default")
      (node (ref "DS6") (pin "2") (pinfunction "f_2") (pintype "passive"))
      (node (ref "IC6") (pin "5") (pinfunction "Q5_5") (pintype "bidirectional"))
    )
    (net (code "59") (name "Net-(DS6-g)") (class "Default")
      (node (ref "DS6") (pin "11") (pinfunction "g_11") (pintype "passive"))
      (node (ref "IC6") (pin "6") (pinfunction "Q6_6") (pintype "bidirectional"))
    )
    (net (code "60") (name "Net-(DS7-DP)") (class "Default")
      (node (ref "DS7") (pin "9") (pinfunction "DP_9") (pintype "passive"))
      (node (ref "IC7") (pin "7") (pinfunction "Q7_7") (pintype "bidirectional"))
    )
    (net (code "61") (name "Net-(DS7-a)") (class "Default")
      (node (ref "DS7") (pin "1") (pinfunction "a_1") (pintype "passive"))
      (node (ref "IC7") (pin "15") (pinfunction "Q0_15") (pintype "bidirectional"))
    )
    (net (code "62") (name "Net-(DS7-b)") (class "Default")
      (node (ref "DS7") (pin "13") (pinfunction "b_13") (pintype "passive"))
      (node (ref "IC7") (pin "1") (pinfunction "Q1_1") (pintype "bidirectional"))
    )
    (net (code "63") (name "Net-(DS7-c)") (class "Default")
      (node (ref "DS7") (pin "10") (pinfunction "c_10") (pintype "passive"))
      (node (ref "IC7") (pin "2") (pinfunction "Q2_2") (pintype "bidirectional"))
    )
    (net (code "64") (name "Net-(DS7-d)") (class "Default")
      (node (ref "DS7") (pin "8") (pinfunction "d_8") (pintype "passive"))
      (node (ref "IC7") (pin "3") (pinfunction "Q3_3") (pintype "bidirectional"))
    )
    (net (code "65") (name "Net-(DS7-e)") (class "Default")
      (node (ref "DS7") (pin "7") (pinfunction "e_7") (pintype "passive"))
      (node (ref "IC7") (pin "4") (pinfunction "Q4_4") (pintype "bidirectional"))
    )
    (net (code "66") (name "Net-(DS7-f)") (class "Default")
      (node (ref "DS7") (pin "2") (pinfunction "f_2") (pintype "passive"))
      (node (ref "IC7") (pin "5") (pinfunction "Q5_5") (pintype "bidirectional"))
    )
    (net (code "67") (name "Net-(DS7-g)") (class "Default")
      (node (ref "DS7") (pin "11") (pinfunction "g_11") (pintype "passive"))
      (node (ref "IC7") (pin "6") (pinfunction "Q6_6") (pintype "bidirectional"))
    )
    (net (code "68") (name "Net-(DS8-DP)") (class "Default")
      (node (ref "DS8") (pin "9") (pinfunction "DP_9") (pintype "passive"))
      (node (ref "IC8") (pin "7") (pinfunction "Q7_7") (pintype "bidirectional"))
    )
    (net (code "69") (name "Net-(DS8-a)") (class "Default")
      (node (ref "DS8") (pin "1") (pinfunction "a_1") (pintype "passive"))
      (node (ref "IC8") (pin "15") (pinfunction "Q0_15") (pintype "bidirectional"))
    )
    (net (code "70") (name "Net-(DS8-b)") (class "Default")
      (node (ref "DS8") (pin "13") (pinfunction "b_13") (pintype "passive"))
      (node (ref "IC8") (pin "1") (pinfunction "Q1_1") (pintype "bidirectional"))
    )
    (net (code "71") (name "Net-(DS8-c)") (class "Default")
      (node (ref "DS8") (pin "10") (pinfunction "c_10") (pintype "passive"))
      (node (ref "IC8") (pin "2") (pinfunction "Q2_2") (pintype "bidirectional"))
    )
    (net (code "72") (name "Net-(DS8-d)") (class "Default")
      (node (ref "DS8") (pin "8") (pinfunction "d_8") (pintype "passive"))
      (node (ref "IC8") (pin "3") (pinfunction "Q3_3") (pintype "bidirectional"))
    )
    (net (code "73") (name "Net-(DS8-e)") (class "Default")
      (node (ref "DS8") (pin "7") (pinfunction "e_7") (pintype "passive"))
      (node (ref "IC8") (pin "4") (pinfunction "Q4_4") (pintype "bidirectional"))
    )
    (net (code "74") (name "Net-(DS8-f)") (class "Default")
      (node (ref "DS8") (pin "2") (pinfunction "f_2") (pintype "passive"))
      (node (ref "IC8") (pin "5") (pinfunction "Q5_5") (pintype "bidirectional"))
    )
    (net (code "75") (name "Net-(DS8-g)") (class "Default")
      (node (ref "DS8") (pin "11") (pinfunction "g_11") (pintype "passive"))
      (node (ref "IC8") (pin "6") (pinfunction "Q6_6") (pintype "bidirectional"))
    )
    (net (code "76") (name "Net-(IC1-DS)") (class "Default")
      (node (ref "IC1") (pin "14") (pinfunction "DS_14") (pintype "bidirectional"))
      (node (ref "U1") (pin "4") (pinfunction "PB15_4") (pintype "passive"))
    )
    (net (code "77") (name "Net-(IC1-Q7S)") (class "Default")
      (node (ref "IC1") (pin "9") (pinfunction "Q7S_9") (pintype "bidirectional"))
      (node (ref "IC2") (pin "14") (pinfunction "DS_14") (pintype "bidirectional"))
    )
    (net (code "78") (name "Net-(IC1-SHCP)") (class "Default")
      (node (ref "IC1") (pin "11") (pinfunction "SHCP_11") (pintype "bidirectional"))
      (node (ref "IC2") (pin "11") (pinfunction "SHCP_11") (pintype "bidirectional"))
      (node (ref "U1") (pin "2") (pinfunction "PB13_2") (pintype "passive"))
    )
    (net (code "79") (name "Net-(IC1-STCP)") (class "Default")
      (node (ref "IC1") (pin "12") (pinfunction "STCP_12") (pintype "bidirectional"))
      (node (ref "IC2") (pin "12") (pinfunction "STCP_12") (pintype "bidirectional"))
      (node (ref "U1") (pin "1") (pinfunction "PB12_1") (pintype "passive"))
    )
    (net (code "80") (name "Net-(IC3-DS)") (class "Default")
      (node (ref "IC3") (pin "14") (pinfunction "DS_14") (pintype "bidirectional"))
      (node (ref "U6") (pin "4") (pinfunction "PB15_4") (pintype "passive"))
    )
    (net (code "81") (name "Net-(IC3-Q7S)") (class "Default")
      (node (ref "IC3") (pin "9") (pinfunction "Q7S_9") (pintype "bidirectional"))
      (node (ref "IC4") (pin "14") (pinfunction "DS_14") (pintype "bidirectional"))
    )
    (net (code "82") (name "Net-(IC3-SHCP)") (class "Default")
      (node (ref "IC3") (pin "11") (pinfunction "SHCP_11") (pintype "bidirectional"))
      (node (ref "IC4") (pin "11") (pinfunction "SHCP_11") (pintype "bidirectional"))
      (node (ref "U6") (pin "2") (pinfunction "PB13_2") (pintype "passive"))
    )
    (net (code "83") (name "Net-(IC3-STCP)") (class "Default")
      (node (ref "IC3") (pin "12") (pinfunction "STCP_12") (pintype "bidirectional"))
      (node (ref "IC4") (pin "12") (pinfunction "STCP_12") (pintype "bidirectional"))
      (node (ref "U6") (pin "1") (pinfunction "PB12_1") (pintype "passive"))
    )
    (net (code "84") (name "Net-(IC5-DS)") (class "Default")
      (node (ref "IC5") (pin "14") (pinfunction "DS_14") (pintype "bidirectional"))
      (node (ref "U10") (pin "4") (pinfunction "PB15_4") (pintype "passive"))
    )
    (net (code "85") (name "Net-(IC5-Q7S)") (class "Default")
      (node (ref "IC5") (pin "9") (pinfunction "Q7S_9") (pintype "bidirectional"))
      (node (ref "IC6") (pin "14") (pinfunction "DS_14") (pintype "bidirectional"))
    )
    (net (code "86") (name "Net-(IC5-SHCP)") (class "Default")
      (node (ref "IC5") (pin "11") (pinfunction "SHCP_11") (pintype "bidirectional"))
      (node (ref "IC6") (pin "11") (pinfunction "SHCP_11") (pintype "bidirectional"))
      (node (ref "U10") (pin "2") (pinfunction "PB13_2") (pintype "passive"))
    )
    (net (code "87") (name "Net-(IC5-STCP)") (class "Default")
      (node (ref "IC5") (pin "12") (pinfunction "STCP_12") (pintype "bidirectional"))
      (node (ref "IC6") (pin "12") (pinfunction "STCP_12") (pintype "bidirectional"))
      (node (ref "U10") (pin "1") (pinfunction "PB12_1") (pintype "passive"))
    )
    (net (code "88") (name "Net-(IC7-DS)") (class "Default")
      (node (ref "IC7") (pin "14") (pinfunction "DS_14") (pintype "bidirectional"))
      (node (ref "U14") (pin "4") (pinfunction "PB15_4") (pintype "passive"))
    )
    (net (code "89") (name "Net-(IC7-Q7S)") (class "Default")
      (node (ref "IC7") (pin "9") (pinfunction "Q7S_9") (pintype "bidirectional"))
      (node (ref "IC8") (pin "14") (pinfunction "DS_14") (pintype "bidirectional"))
    )
    (net (code "90") (name "Net-(IC7-SHCP)") (class "Default")
      (node (ref "IC7") (pin "11") (pinfunction "SHCP_11") (pintype "bidirectional"))
      (node (ref "IC8") (pin "11") (pinfunction "SHCP_11") (pintype "bidirectional"))
      (node (ref "U14") (pin "2") (pinfunction "PB13_2") (pintype "passive"))
    )
    (net (code "91") (name "Net-(IC7-STCP)") (class "Default")
      (node (ref "IC7") (pin "12") (pinfunction "STCP_12") (pintype "bidirectional"))
      (node (ref "IC8") (pin "12") (pinfunction "STCP_12") (pintype "bidirectional"))
      (node (ref "U14") (pin "1") (pinfunction "PB12_1") (pintype "passive"))
    )
    (net (code "92") (name "Net-(U1-PA0)") (class "Default")
      (node (ref "U1") (pin "25") (pinfunction "PA0_25") (pintype "passive"))
      (node (ref "U2") (pin "8") (pinfunction "~{IRQ}_8") (pintype "input"))
    )
    (net (code "93") (name "Net-(U1-PA3)") (class "Default")
      (node (ref "U1") (pin "28") (pinfunction "PA3_28") (pintype "passive"))
      (node (ref "U2") (pin "3") (pinfunction "CE_3") (pintype "input"))
    )
    (net (code "94") (name "Net-(U1-PA4)") (class "Default")
      (node (ref "U1") (pin "29") (pinfunction "PA4_29") (pintype "passive"))
      (node (ref "U2") (pin "4") (pinfunction "~{CSN}_4") (pintype "input"))
    )
    (net (code "95") (name "Net-(U1-PA5)") (class "Default")
      (node (ref "U1") (pin "30") (pinfunction "PA5_30") (pintype "passive"))
      (node (ref "U2") (pin "5") (pinfunction "SCK_5") (pintype "input"))
    )
    (net (code "96") (name "Net-(U1-PA6)") (class "Default")
      (node (ref "U1") (pin "31") (pinfunction "PA6_31") (pintype "passive"))
      (node (ref "U2") (pin "7") (pinfunction "MISO_7") (pintype "input"))
    )
    (net (code "97") (name "Net-(U1-PA7)") (class "Default")
      (node (ref "U1") (pin "32") (pinfunction "PA7_32") (pintype "passive"))
      (node (ref "U2") (pin "6") (pinfunction "MOSI_6") (pintype "input"))
    )
    (net (code "98") (name "Net-(U1-PA8)") (class "Default")
      (node (ref "D3") (pin "1") (pinfunction "1_1") (pintype "passive"))
      (node (ref "U1") (pin "5") (pinfunction "PA8_5") (pintype "passive"))
    )
    (net (code "99") (name "Net-(U1-PA10)") (class "Default")
      (node (ref "D1") (pin "A") (pinfunction "A_A") (pintype "passive"))
      (node (ref "U1") (pin "7") (pinfunction "PA10_7") (pintype "passive"))
    )
    (net (code "100") (name "Net-(U1-PB5)") (class "Default")
      (node (ref "S1") (pin "1") (pinfunction "1_1") (pintype "passive"))
      (node (ref "U1") (pin "13") (pinfunction "PB5_13") (pintype "passive"))
    )
    (net (code "101") (name "Net-(U1-PB6)") (class "Default")
      (node (ref "S2") (pin "1") (pinfunction "1_1") (pintype "passive"))
      (node (ref "U1") (pin "14") (pinfunction "PB6_14") (pintype "passive"))
    )
    (net (code "102") (name "Net-(U1-PB7)") (class "Default")
      (node (ref "S3") (pin "1") (pinfunction "1_1") (pintype "passive"))
      (node (ref "U1") (pin "15") (pinfunction "PB7_15") (pintype "passive"))
    )
    (net (code "103") (name "Net-(U1-PB8)") (class "Default")
      (node (ref "S4") (pin "1") (pinfunction "1_1") (pintype "passive"))
      (node (ref "U1") (pin "16") (pinfunction "PB8_16") (pintype "passive"))
    )
    (net (code "104") (name "Net-(U1-PB9)") (class "Default")
      (node (ref "S5") (pin "1") (pinfunction "1_1") (pintype "passive"))
      (node (ref "U1") (pin "17") (pinfunction "PB9_17") (pintype "passive"))
    )
    (net (code "105") (name "Net-(U1-PB10)") (class "Default")
      (node (ref "PCF8574") (pin "17") (pinfunction "17_17") (pintype "passive"))
      (node (ref "U1") (pin "35") (pinfunction "PB10_35") (pintype "passive"))
    )
    (net (code "106") (name "Net-(U1-PB11)") (class "Default")
      (node (ref "PCF8574") (pin "18") (pinfunction "18_18") (pintype "passive"))
      (node (ref "U1") (pin "36") (pinfunction "PB11_36") (pintype "passive"))
    )
    (net (code "107") (name "Net-(U5-A)") (class "Default")
      (node (ref "PCF8574") (pin "15") (pinfunction "15_15") (pintype "passive"))
      (node (ref "U5") (pin "15") (pinfunction "A_15") (pintype "power_in"))
    )
    (net (code "108") (name "Net-(U5-DB0)") (class "Default")
      (node (ref "PCF8574") (pin "7") (pinfunction "7_7") (pintype "passive"))
      (node (ref "U5") (pin "7") (pinfunction "DB0_7") (pintype "bidirectional"))
    )
    (net (code "109") (name "Net-(U5-DB1)") (class "Default")
      (node (ref "PCF8574") (pin "8") (pinfunction "8_8") (pintype "passive"))
      (node (ref "U5") (pin "8") (pinfunction "DB1_8") (pintype "bidirectional"))
    )
    (net (code "110") (name "Net-(U5-DB2)") (class "Default")
      (node (ref "PCF8574") (pin "9") (pinfunction "9_9") (pintype "passive"))
      (node (ref "U5") (pin "9") (pinfunction "DB2_9") (pintype "bidirectional"))
    )
    (net (code "111") (name "Net-(U5-DB3)") (class "Default")
      (node (ref "PCF8574") (pin "10") (pinfunction "10_10") (pintype "passive"))
      (node (ref "U5") (pin "10") (pinfunction "DB3_10") (pintype "bidirectional"))
    )
    (net (code "112") (name "Net-(U5-DB4)") (class "Default")
      (node (ref "PCF8574") (pin "11") (pinfunction "11_11") (pintype "passive"))
      (node (ref "U5") (pin "11") (pinfunction "DB4_11") (pintype "bidirectional"))
    )
    (net (code "113") (name "Net-(U5-DB5)") (class "Default")
      (node (ref "PCF8574") (pin "12") (pinfunction "12_12") (pintype "passive"))
      (node (ref "U5") (pin "12") (pinfunction "DB5_12") (pintype "bidirectional"))
    )
    (net (code "114") (name "Net-(U5-DB6)") (class "Default")
      (node (ref "PCF8574") (pin "13") (pinfunction "13_13") (pintype "passive"))
      (node (ref "U5") (pin "13") (pinfunction "DB6_13") (pintype "bidirectional"))
    )
    (net (code "115") (name "Net-(U5-DB7)") (class "Default")
      (node (ref "PCF8574") (pin "14") (pinfunction "14_14") (pintype "passive"))
      (node (ref "U5") (pin "14") (pinfunction "DB7_14") (pintype "bidirectional"))
    )
    (net (code "116") (name "Net-(U5-E)") (class "Default")
      (node (ref "PCF8574") (pin "6") (pinfunction "6_6") (pintype "passive"))
      (node (ref "U5") (pin "6") (pinfunction "E_6") (pintype "input"))
    )
    (net (code "117") (name "Net-(U5-K)") (class "Default")
      (node (ref "PCF8574") (pin "16") (pinfunction "16_16") (pintype "passive"))
      (node (ref "U5") (pin "16") (pinfunction "K_16") (pintype "power_in"))
    )
    (net (code "118") (name "Net-(U5-RS)") (class "Default")
      (node (ref "PCF8574") (pin "4") (pinfunction "4_4") (pintype "passive"))
      (node (ref "U5") (pin "4") (pinfunction "RS_4") (pintype "input"))
    )
    (net (code "119") (name "Net-(U5-R{slash}W)") (class "Default")
      (node (ref "PCF8574") (pin "5") (pinfunction "5_5") (pintype "passive"))
      (node (ref "U5") (pin "5") (pinfunction "R/W_5") (pintype "input"))
    )
    (net (code "120") (name "Net-(U5-VDD)") (class "Default")
      (node (ref "PCF8574") (pin "2") (pinfunction "2_2") (pintype "passive"))
      (node (ref "U5") (pin "2") (pinfunction "VDD_2") (pintype "power_in"))
    )
    (net (code "121") (name "Net-(U5-VO)") (class "Default")
      (node (ref "PCF8574") (pin "3") (pinfunction "3_3") (pintype "passive"))
      (node (ref "U5") (pin "3") (pinfunction "VO_3") (pintype "bidirectional"))
    )
    (net (code "122") (name "Net-(U5-VSS)") (class "Default")
      (node (ref "PCF8574") (pin "1") (pinfunction "1_1") (pintype "passive"))
      (node (ref "U5") (pin "1") (pinfunction "VSS_1") (pintype "power_in"))
    )
    (net (code "123") (name "Net-(U6-PA0)") (class "Default")
      (node (ref "U6") (pin "25") (pinfunction "PA0_25") (pintype "passive"))
      (node (ref "U7") (pin "8") (pinfunction "~{IRQ}_8") (pintype "input"))
    )
    (net (code "124") (name "Net-(U6-PA3)") (class "Default")
      (node (ref "U6") (pin "28") (pinfunction "PA3_28") (pintype "passive"))
      (node (ref "U7") (pin "3") (pinfunction "CE_3") (pintype "input"))
    )
    (net (code "125") (name "Net-(U6-PA4)") (class "Default")
      (node (ref "U6") (pin "29") (pinfunction "PA4_29") (pintype "passive"))
      (node (ref "U7") (pin "4") (pinfunction "~{CSN}_4") (pintype "input"))
    )
    (net (code "126") (name "Net-(U6-PA5)") (class "Default")
      (node (ref "U6") (pin "30") (pinfunction "PA5_30") (pintype "passive"))
      (node (ref "U7") (pin "5") (pinfunction "SCK_5") (pintype "input"))
    )
    (net (code "127") (name "Net-(U6-PA6)") (class "Default")
      (node (ref "U6") (pin "31") (pinfunction "PA6_31") (pintype "passive"))
      (node (ref "U7") (pin "7") (pinfunction "MISO_7") (pintype "input"))
    )
    (net (code "128") (name "Net-(U6-PA7)") (class "Default")
      (node (ref "U6") (pin "32") (pinfunction "PA7_32") (pintype "passive"))
      (node (ref "U7") (pin "6") (pinfunction "MOSI_6") (pintype "input"))
    )
    (net (code "129") (name "Net-(U6-PA8)") (class "Default")
      (node (ref "D6") (pin "1") (pinfunction "1_1") (pintype "passive"))
      (node (ref "U6") (pin "5") (pinfunction "PA8_5") (pintype "passive"))
    )
    (net (code "130") (name "Net-(U6-PA10)") (class "Default")
      (node (ref "D4") (pin "A") (pinfunction "A_A") (pintype "passive"))
      (node (ref "U6") (pin "7") (pinfunction "PA10_7") (pintype "passive"))
    )
    (net (code "131") (name "Net-(U10-PA0)") (class "Default")
      (node (ref "U10") (pin "25") (pinfunction "PA0_25") (pintype "passive"))
      (node (ref "U11") (pin "8") (pinfunction "~{IRQ}_8") (pintype "input"))
    )
    (net (code "132") (name "Net-(U10-PA3)") (class "Default")
      (node (ref "U10") (pin "28") (pinfunction "PA3_28") (pintype "passive"))
      (node (ref "U11") (pin "3") (pinfunction "CE_3") (pintype "input"))
    )
    (net (code "133") (name "Net-(U10-PA4)") (class "Default")
      (node (ref "U10") (pin "29") (pinfunction "PA4_29") (pintype "passive"))
      (node (ref "U11") (pin "4") (pinfunction "~{CSN}_4") (pintype "input"))
    )
    (net (code "134") (name "Net-(U10-PA5)") (class "Default")
      (node (ref "U10") (pin "30") (pinfunction "PA5_30") (pintype "passive"))
      (node (ref "U11") (pin "5") (pinfunction "SCK_5") (pintype "input"))
    )
    (net (code "135") (name "Net-(U10-PA6)") (class "Default")
      (node (ref "U10") (pin "31") (pinfunction "PA6_31") (pintype "passive"))
      (node (ref "U11") (pin "7") (pinfunction "MISO_7") (pintype "input"))
    )
    (net (code "136") (name "Net-(U10-PA7)") (class "Default")
      (node (ref "U10") (pin "32") (pinfunction "PA7_32") (pintype "passive"))
      (node (ref "U11") (pin "6") (pinfunction "MOSI_6") (pintype "input"))
    )
    (net (code "137") (name "Net-(U10-PA8)") (class "Default")
      (node (ref "D9") (pin "1") (pinfunction "1_1") (pintype "passive"))
      (node (ref "U10") (pin "5") (pinfunction "PA8_5") (pintype "passive"))
    )
    (net (code "138") (name "Net-(U10-PA10)") (class "Default")
      (node (ref "D7") (pin "A") (pinfunction "A_A") (pintype "passive"))
      (node (ref "U10") (pin "7") (pinfunction "PA10_7") (pintype "passive"))
    )
    (net (code "139") (name "Net-(U14-PA0)") (class "Default")
      (node (ref "U14") (pin "25") (pinfunction "PA0_25") (pintype "passive"))
      (node (ref "U15") (pin "8") (pinfunction "~{IRQ}_8") (pintype "input"))
    )
    (net (code "140") (name "Net-(U14-PA3)") (class "Default")
      (node (ref "U14") (pin "28") (pinfunction "PA3_28") (pintype "passive"))
      (node (ref "U15") (pin "3") (pinfunction "CE_3") (pintype "input"))
    )
    (net (code "141") (name "Net-(U14-PA4)") (class "Default")
      (node (ref "U14") (pin "29") (pinfunction "PA4_29") (pintype "passive"))
      (node (ref "U15") (pin "4") (pinfunction "~{CSN}_4") (pintype "input"))
    )
    (net (code "142") (name "Net-(U14-PA5)") (class "Default")
      (node (ref "U14") (pin "30") (pinfunction "PA5_30") (pintype "passive"))
      (node (ref "U15") (pin "5") (pinfunction "SCK_5") (pintype "input"))
    )
    (net (code "143") (name "Net-(U14-PA6)") (class "Default")
      (node (ref "U14") (pin "31") (pinfunction "PA6_31") (pintype "passive"))
      (node (ref "U15") (pin "7") (pinfunction "MISO_7") (pintype "input"))
    )
    (net (code "144") (name "Net-(U14-PA7)") (class "Default")
      (node (ref "U14") (pin "32") (pinfunction "PA7_32") (pintype "passive"))
      (node (ref "U15") (pin "6") (pinfunction "MOSI_6") (pintype "input"))
    )
    (net (code "145") (name "Net-(U14-PA8)") (class "Default")
      (node (ref "D12") (pin "1") (pinfunction "1_1") (pintype "passive"))
      (node (ref "U14") (pin "5") (pinfunction "PA8_5") (pintype "passive"))
    )
    (net (code "146") (name "Net-(U14-PA10)") (class "Default")
      (node (ref "D10") (pin "A") (pinfunction "A_A") (pintype "passive"))
      (node (ref "U14") (pin "7") (pinfunction "PA10_7") (pintype "passive"))
    )
    (net (code "147") (name "unconnected-(IC1-~{MR}-Pad10)") (class "Default")
      (node (ref "IC1") (pin "10") (pinfunction "~{MR}_10") (pintype "bidirectional"))
    )
    (net (code "148") (name "unconnected-(IC2-Q7S-Pad9)") (class "Default")
      (node (ref "IC2") (pin "9") (pinfunction "Q7S_9") (pintype "bidirectional"))
    )
    (net (code "149") (name "unconnected-(IC2-~{MR}-Pad10)") (class "Default")
      (node (ref "IC2") (pin "10") (pinfunction "~{MR}_10") (pintype "bidirectional"))
    )
    (net (code "150") (name "unconnected-(IC3-~{MR}-Pad10)") (class "Default")
      (node (ref "IC3") (pin "10") (pinfunction "~{MR}_10") (pintype "bidirectional"))
    )
    (net (code "151") (name "unconnected-(IC4-Q7S-Pad9)") (class "Default")
      (node (ref "IC4") (pin "9") (pinfunction "Q7S_9") (pintype "bidirectional"))
    )
    (net (code "152") (name "unconnected-(IC4-~{MR}-Pad10)") (class "Default")
      (node (ref "IC4") (pin "10") (pinfunction "~{MR}_10") (pintype "bidirectional"))
    )
    (net (code "153") (name "unconnected-(IC5-~{MR}-Pad10)") (class "Default")
      (node (ref "IC5") (pin "10") (pinfunction "~{MR}_10") (pintype "bidirectional"))
    )
    (net (code "154") (name "unconnected-(IC6-Q7S-Pad9)") (class "Default")
      (node (ref "IC6") (pin "9") (pinfunction "Q7S_9") (pintype "bidirectional"))
    )
    (net (code "155") (name "unconnected-(IC6-~{MR}-Pad10)") (class "Default")
      (node (ref "IC6") (pin "10") (pinfunction "~{MR}_10") (pintype "bidirectional"))
    )
    (net (code "156") (name "unconnected-(IC7-~{MR}-Pad10)") (class "Default")
      (node (ref "IC7") (pin "10") (pinfunction "~{MR}_10") (pintype "bidirectional"))
    )
    (net (code "157") (name "unconnected-(IC8-Q7S-Pad9)") (class "Default")
      (node (ref "IC8") (pin "9") (pinfunction "Q7S_9") (pintype "bidirectional"))
    )
    (net (code "158") (name "unconnected-(IC8-~{MR}-Pad10)") (class "Default")
      (node (ref "IC8") (pin "10") (pinfunction "~{MR}_10") (pintype "bidirectional"))
    )
    (net (code "159") (name "unconnected-(S1-Pad2)") (class "Default")
      (node (ref "S1") (pin "2") (pinfunction "2_2") (pintype "passive"))
    )
    (net (code "160") (name "unconnected-(S1-Pad4)") (class "Default")
      (node (ref "S1") (pin "4") (pinfunction "4_4") (pintype "passive"))
    )
    (net (code "161") (name "unconnected-(S2-Pad2)") (class "Default")
      (node (ref "S2") (pin "2") (pinfunction "2_2") (pintype "passive"))
    )
    (net (code "162") (name "unconnected-(S2-Pad4)") (class "Default")
      (node (ref "S2") (pin "4") (pinfunction "4_4") (pintype "passive"))
    )
    (net (code "163") (name "unconnected-(S3-Pad2)") (class "Default")
      (node (ref "S3") (pin "2") (pinfunction "2_2") (pintype "passive"))
    )
    (net (code "164") (name "unconnected-(S3-Pad4)") (class "Default")
      (node (ref "S3") (pin "4") (pinfunction "4_4") (pintype "passive"))
    )
    (net (code "165") (name "unconnected-(S4-Pad2)") (class "Default")
      (node (ref "S4") (pin "2") (pinfunction "2_2") (pintype "passive"))
    )
    (net (code "166") (name "unconnected-(S4-Pad4)") (class "Default")
      (node (ref "S4") (pin "4") (pinfunction "4_4") (pintype "passive"))
    )
    (net (code "167") (name "unconnected-(S5-Pad2)") (class "Default")
      (node (ref "S5") (pin "2") (pinfunction "2_2") (pintype "passive"))
    )
    (net (code "168") (name "unconnected-(S5-Pad4)") (class "Default")
      (node (ref "S5") (pin "4") (pinfunction "4_4") (pintype "passive"))
    )
    (net (code "169") (name "unconnected-(S6-Pad2)") (class "Default")
      (node (ref "S6") (pin "2") (pinfunction "2_2") (pintype "passive"))
    )
    (net (code "170") (name "unconnected-(S6-Pad4)") (class "Default")
      (node (ref "S6") (pin "4") (pinfunction "4_4") (pintype "passive"))
    )
    (net (code "171") (name "unconnected-(S7-Pad2)") (class "Default")
      (node (ref "S7") (pin "2") (pinfunction "2_2") (pintype "passive"))
    )
    (net (code "172") (name "unconnected-(S7-Pad4)") (class "Default")
      (node (ref "S7") (pin "4") (pinfunction "4_4") (pintype "passive"))
    )
    (net (code "173") (name "unconnected-(S8-Pad2)") (class "Default")
      (node (ref "S8") (pin "2") (pinfunction "2_2") (pintype "passive"))
    )
    (net (code "174") (name "unconnected-(S8-Pad4)") (class "Default")
      (node (ref "S8") (pin "4") (pinfunction "4_4") (pintype "passive"))
    )
    (net (code "175") (name "unconnected-(S9-Pad2)") (class "Default")
      (node (ref "S9") (pin "2") (pinfunction "2_2") (pintype "passive"))
    )
    (net (code "176") (name "unconnected-(S9-Pad4)") (class "Default")
      (node (ref "S9") (pin "4") (pinfunction "4_4") (pintype "passive"))
    )
    (net (code "177") (name "unconnected-(U1-3V3-Pad20)") (class "Default")
      (node (ref "U1") (pin "20") (pinfunction "3V3_20") (pintype "passive"))
    )
    (net (code "178") (name "unconnected-(U1-3V3-Pad38)") (class "Default")
      (node (ref "U1") (pin "38") (pinfunction "3V3_38") (pintype "passive"))
    )
    (net (code "179") (name "unconnected-(U1-GND-Pad19)") (class "Default")
      (node (ref "U1") (pin "19") (pinfunction "GND_19") (pintype "passive"))
    )
    (net (code "180") (name "unconnected-(U1-PA1-Pad26)") (class "Default")
      (node (ref "U1") (pin "26") (pinfunction "PA1_26") (pintype "passive"))
    )
    (net (code "181") (name "unconnected-(U1-PA2-Pad27)") (class "Default")
      (node (ref "U1") (pin "27") (pinfunction "PA2_27") (pintype "passive"))
    )
    (net (code "182") (name "unconnected-(U1-PA11-Pad8)") (class "Default")
      (node (ref "U1") (pin "8") (pinfunction "PA11_8") (pintype "passive"))
    )
    (net (code "183") (name "unconnected-(U1-PA12-Pad9)") (class "Default")
      (node (ref "U1") (pin "9") (pinfunction "PA12_9") (pintype "passive"))
    )
    (net (code "184") (name "unconnected-(U1-PA15-Pad10)") (class "Default")
      (node (ref "U1") (pin "10") (pinfunction "PA15_10") (pintype "passive"))
    )
    (net (code "185") (name "unconnected-(U1-PB0-Pad33)") (class "Default")
      (node (ref "U1") (pin "33") (pinfunction "PB0_33") (pintype "passive"))
    )
    (net (code "186") (name "unconnected-(U1-PB1-Pad34)") (class "Default")
      (node (ref "U1") (pin "34") (pinfunction "PB1_34") (pintype "passive"))
    )
    (net (code "187") (name "unconnected-(U1-PB3-Pad11)") (class "Default")
      (node (ref "U1") (pin "11") (pinfunction "PB3_11") (pintype "passive"))
    )
    (net (code "188") (name "unconnected-(U1-PB4-Pad12)") (class "Default")
      (node (ref "U1") (pin "12") (pinfunction "PB4_12") (pintype "passive"))
    )
    (net (code "189") (name "unconnected-(U1-PB14-Pad3)") (class "Default")
      (node (ref "U1") (pin "3") (pinfunction "PB14_3") (pintype "passive"))
    )
    (net (code "190") (name "unconnected-(U1-PC13-Pad22)") (class "Default")
      (node (ref "U1") (pin "22") (pinfunction "PC13_22") (pintype "passive"))
    )
    (net (code "191") (name "unconnected-(U1-PC14-Pad23)") (class "Default")
      (node (ref "U1") (pin "23") (pinfunction "PC14_23") (pintype "passive"))
    )
    (net (code "192") (name "unconnected-(U1-PC15-Pad24)") (class "Default")
      (node (ref "U1") (pin "24") (pinfunction "PC15_24") (pintype "passive"))
    )
    (net (code "193") (name "unconnected-(U1-VBAT-Pad21)") (class "Default")
      (node (ref "U1") (pin "21") (pinfunction "VBAT_21") (pintype "passive"))
    )
    (net (code "194") (name "unconnected-(U6-3V3-Pad20)") (class "Default")
      (node (ref "U6") (pin "20") (pinfunction "3V3_20") (pintype "passive"))
    )
    (net (code "195") (name "unconnected-(U6-3V3-Pad38)") (class "Default")
      (node (ref "U6") (pin "38") (pinfunction "3V3_38") (pintype "passive"))
    )
    (net (code "196") (name "unconnected-(U6-GND-Pad19)") (class "Default")
      (node (ref "U6") (pin "19") (pinfunction "GND_19") (pintype "passive"))
    )
    (net (code "197") (name "unconnected-(U6-PA1-Pad26)") (class "Default")
      (node (ref "U6") (pin "26") (pinfunction "PA1_26") (pintype "passive"))
    )
    (net (code "198") (name "unconnected-(U6-PA2-Pad27)") (class "Default")
      (node (ref "U6") (pin "27") (pinfunction "PA2_27") (pintype "passive"))
    )
    (net (code "199") (name "unconnected-(U6-PA11-Pad8)") (class "Default")
      (node (ref "U6") (pin "8") (pinfunction "PA11_8") (pintype "passive"))
    )
    (net (code "200") (name "unconnected-(U6-PA12-Pad9)") (class "Default")
      (node (ref "U6") (pin "9") (pinfunction "PA12_9") (pintype "passive"))
    )
    (net (code "201") (name "unconnected-(U6-PA15-Pad10)") (class "Default")
      (node (ref "U6") (pin "10") (pinfunction "PA15_10") (pintype "passive"))
    )
    (net (code "202") (name "unconnected-(U6-PB0-Pad33)") (class "Default")
      (node (ref "U6") (pin "33") (pinfunction "PB0_33") (pintype "passive"))
    )
    (net (code "203") (name "unconnected-(U6-PB1-Pad34)") (class "Default")
      (node (ref "U6") (pin "34") (pinfunction "PB1_34") (pintype "passive"))
    )
    (net (code "204") (name "unconnected-(U6-PB3-Pad11)") (class "Default")
      (node (ref "U6") (pin "11") (pinfunction "PB3_11") (pintype "passive"))
    )
    (net (code "205") (name "unconnected-(U6-PB4-Pad12)") (class "Default")
      (node (ref "U6") (pin "12") (pinfunction "PB4_12") (pintype "passive"))
    )
    (net (code "206") (name "unconnected-(U6-PB5-Pad13)") (class "Default")
      (node (ref "U6") (pin "13") (pinfunction "PB5_13") (pintype "passive"))
    )
    (net (code "207") (name "unconnected-(U6-PB6-Pad14)") (class "Default")
      (node (ref "U6") (pin "14") (pinfunction "PB6_14") (pintype "passive"))
    )
    (net (code "208") (name "unconnected-(U6-PB7-Pad15)") (class "Default")
      (node (ref "U6") (pin "15") (pinfunction "PB7_15") (pintype "passive"))
    )
    (net (code "209") (name "unconnected-(U6-PB8-Pad16)") (class "Default")
      (node (ref "U6") (pin "16") (pinfunction "PB8_16") (pintype "passive"))
    )
    (net (code "210") (name "unconnected-(U6-PB9-Pad17)") (class "Default")
      (node (ref "U6") (pin "17") (pinfunction "PB9_17") (pintype "passive"))
    )
    (net (code "211") (name "unconnected-(U6-PB10-Pad35)") (class "Default")
      (node (ref "U6") (pin "35") (pinfunction "PB10_35") (pintype "passive"))
    )
    (net (code "212") (name "unconnected-(U6-PB11-Pad36)") (class "Default")
      (node (ref "U6") (pin "36") (pinfunction "PB11_36") (pintype "passive"))
    )
    (net (code "213") (name "unconnected-(U6-PB14-Pad3)") (class "Default")
      (node (ref "U6") (pin "3") (pinfunction "PB14_3") (pintype "passive"))
    )
    (net (code "214") (name "unconnected-(U6-PC13-Pad22)") (class "Default")
      (node (ref "U6") (pin "22") (pinfunction "PC13_22") (pintype "passive"))
    )
    (net (code "215") (name "unconnected-(U6-PC14-Pad23)") (class "Default")
      (node (ref "U6") (pin "23") (pinfunction "PC14_23") (pintype "passive"))
    )
    (net (code "216") (name "unconnected-(U6-PC15-Pad24)") (class "Default")
      (node (ref "U6") (pin "24") (pinfunction "PC15_24") (pintype "passive"))
    )
    (net (code "217") (name "unconnected-(U6-VBAT-Pad21)") (class "Default")
      (node (ref "U6") (pin "21") (pinfunction "VBAT_21") (pintype "passive"))
    )
    (net (code "218") (name "unconnected-(U10-3V3-Pad20)") (class "Default")
      (node (ref "U10") (pin "20") (pinfunction "3V3_20") (pintype "passive"))
    )
    (net (code "219") (name "unconnected-(U10-3V3-Pad38)") (class "Default")
      (node (ref "U10") (pin "38") (pinfunction "3V3_38") (pintype "passive"))
    )
    (net (code "220") (name "unconnected-(U10-GND-Pad19)") (class "Default")
      (node (ref "U10") (pin "19") (pinfunction "GND_19") (pintype "passive"))
    )
    (net (code "221") (name "unconnected-(U10-PA1-Pad26)") (class "Default")
      (node (ref "U10") (pin "26") (pinfunction "PA1_26") (pintype "passive"))
    )
    (net (code "222") (name "unconnected-(U10-PA2-Pad27)") (class "Default")
      (node (ref "U10") (pin "27") (pinfunction "PA2_27") (pintype "passive"))
    )
    (net (code "223") (name "unconnected-(U10-PA11-Pad8)") (class "Default")
      (node (ref "U10") (pin "8") (pinfunction "PA11_8") (pintype "passive"))
    )
    (net (code "224") (name "unconnected-(U10-PA12-Pad9)") (class "Default")
      (node (ref "U10") (pin "9") (pinfunction "PA12_9") (pintype "passive"))
    )
    (net (code "225") (name "unconnected-(U10-PA15-Pad10)") (class "Default")
      (node (ref "U10") (pin "10") (pinfunction "PA15_10") (pintype "passive"))
    )
    (net (code "226") (name "unconnected-(U10-PB0-Pad33)") (class "Default")
      (node (ref "U10") (pin "33") (pinfunction "PB0_33") (pintype "passive"))
    )
    (net (code "227") (name "unconnected-(U10-PB1-Pad34)") (class "Default")
      (node (ref "U10") (pin "34") (pinfunction "PB1_34") (pintype "passive"))
    )
    (net (code "228") (name "unconnected-(U10-PB3-Pad11)") (class "Default")
      (node (ref "U10") (pin "11") (pinfunction "PB3_11") (pintype "passive"))
    )
    (net (code "229") (name "unconnected-(U10-PB4-Pad12)") (class "Default")
      (node (ref "U10") (pin "12") (pinfunction "PB4_12") (pintype "passive"))
    )
    (net (code "230") (name "unconnected-(U10-PB5-Pad13)") (class "Default")
      (node (ref "U10") (pin "13") (pinfunction "PB5_13") (pintype "passive"))
    )
    (net (code "231") (name "unconnected-(U10-PB6-Pad14)") (class "Default")
      (node (ref "U10") (pin "14") (pinfunction "PB6_14") (pintype "passive"))
    )
    (net (code "232") (name "unconnected-(U10-PB7-Pad15)") (class "Default")
      (node (ref "U10") (pin "15") (pinfunction "PB7_15") (pintype "passive"))
    )
    (net (code "233") (name "unconnected-(U10-PB8-Pad16)") (class "Default")
      (node (ref "U10") (pin "16") (pinfunction "PB8_16") (pintype "passive"))
    )
    (net (code "234") (name "unconnected-(U10-PB9-Pad17)") (class "Default")
      (node (ref "U10") (pin "17") (pinfunction "PB9_17") (pintype "passive"))
    )
    (net (code "235") (name "unconnected-(U10-PB10-Pad35)") (class "Default")
      (node (ref "U10") (pin "35") (pinfunction "PB10_35") (pintype "passive"))
    )
    (net (code "236") (name "unconnected-(U10-PB11-Pad36)") (class "Default")
      (node (ref "U10") (pin "36") (pinfunction "PB11_36") (pintype "passive"))
    )
    (net (code "237") (name "unconnected-(U10-PB14-Pad3)") (class "Default")
      (node (ref "U10") (pin "3") (pinfunction "PB14_3") (pintype "passive"))
    )
    (net (code "238") (name "unconnected-(U10-PC13-Pad22)") (class "Default")
      (node (ref "U10") (pin "22") (pinfunction "PC13_22") (pintype "passive"))
    )
    (net (code "239") (name "unconnected-(U10-PC14-Pad23)") (class "Default")
      (node (ref "U10") (pin "23") (pinfunction "PC14_23") (pintype "passive"))
    )
    (net (code "240") (name "unconnected-(U10-PC15-Pad24)") (class "Default")
      (node (ref "U10") (pin "24") (pinfunction "PC15_24") (pintype "passive"))
    )
    (net (code "241") (name "unconnected-(U10-VBAT-Pad21)") (class "Default")
      (node (ref "U10") (pin "21") (pinfunction "VBAT_21") (pintype "passive"))
    )
    (net (code "242") (name "unconnected-(U14-3V3-Pad20)") (class "Default")
      (node (ref "U14") (pin "20") (pinfunction "3V3_20") (pintype "passive"))
    )
    (net (code "243") (name "unconnected-(U14-3V3-Pad38)") (class "Default")
      (node (ref "U14") (pin "38") (pinfunction "3V3_38") (pintype "passive"))
    )
    (net (code "244") (name "unconnected-(U14-GND-Pad19)") (class "Default")
      (node (ref "U14") (pin "19") (pinfunction "GND_19") (pintype "passive"))
    )
    (net (code "245") (name "unconnected-(U14-PA1-Pad26)") (class "Default")
      (node (ref "U14") (pin "26") (pinfunction "PA1_26") (pintype "passive"))
    )
    (net (code "246") (name "unconnected-(U14-PA2-Pad27)") (class "Default")
      (node (ref "U14") (pin "27") (pinfunction "PA2_27") (pintype "passive"))
    )
    (net (code "247") (name "unconnected-(U14-PA11-Pad8)") (class "Default")
      (node (ref "U14") (pin "8") (pinfunction "PA11_8") (pintype "passive"))
    )
    (net (code "248") (name "unconnected-(U14-PA12-Pad9)") (class "Default")
      (node (ref "U14") (pin "9") (pinfunction "PA12_9") (pintype "passive"))
    )
    (net (code "249") (name "unconnected-(U14-PA15-Pad10)") (class "Default")
      (node (ref "U14") (pin "10") (pinfunction "PA15_10") (pintype "passive"))
    )
    (net (code "250") (name "unconnected-(U14-PB0-Pad33)") (class "Default")
      (node (ref "U14") (pin "33") (pinfunction "PB0_33") (pintype "passive"))
    )
    (net (code "251") (name "unconnected-(U14-PB1-Pad34)") (class "Default")
      (node (ref "U14") (pin "34") (pinfunction "PB1_34") (pintype "passive"))
    )
    (net (code "252") (name "unconnected-(U14-PB3-Pad11)") (class "Default")
      (node (ref "U14") (pin "11") (pinfunction "PB3_11") (pintype "passive"))
    )
    (net (code "253") (name "unconnected-(U14-PB4-Pad12)") (class "Default")
      (node (ref "U14") (pin "12") (pinfunction "PB4_12") (pintype "passive"))
    )
    (net (code "254") (name "unconnected-(U14-PB5-Pad13)") (class "Default")
      (node (ref "U14") (pin "13") (pinfunction "PB5_13") (pintype "passive"))
    )
    (net (code "255") (name "unconnected-(U14-PB6-Pad14)") (class "Default")
      (node (ref "U14") (pin "14") (pinfunction "PB6_14") (pintype "passive"))
    )
    (net (code "256") (name "unconnected-(U14-PB7-Pad15)") (class "Default")
      (node (ref "U14") (pin "15") (pinfunction "PB7_15") (pintype "passive"))
    )
    (net (code "257") (name "unconnected-(U14-PB8-Pad16)") (class "Default")
      (node (ref "U14") (pin "16") (pinfunction "PB8_16") (pintype "passive"))
    )
    (net (code "258") (name "unconnected-(U14-PB9-Pad17)") (class "Default")
      (node (ref "U14") (pin "17") (pinfunction "PB9_17") (pintype "passive"))
    )
    (net (code "259") (name "unconnected-(U14-PB10-Pad35)") (class "Default")
      (node (ref "U14") (pin "35") (pinfunction "PB10_35") (pintype "passive"))
    )
    (net (code "260") (name "unconnected-(U14-PB11-Pad36)") (class "Default")
      (node (ref "U14") (pin "36") (pinfunction "PB11_36") (pintype "passive"))
    )
    (net (code "261") (name "unconnected-(U14-PB14-Pad3)") (class "Default")
      (node (ref "U14") (pin "3") (pinfunction "PB14_3") (pintype "passive"))
    )
    (net (code "262") (name "unconnected-(U14-PC13-Pad22)") (class "Default")
      (node (ref "U14") (pin "22") (pinfunction "PC13_22") (pintype "passive"))
    )
    (net (code "263") (name "unconnected-(U14-PC14-Pad23)") (class "Default")
      (node (ref "U14") (pin "23") (pinfunction "PC14_23") (pintype "passive"))
    )
    (net (code "264") (name "unconnected-(U14-PC15-Pad24)") (class "Default")
      (node (ref "U14") (pin "24") (pinfunction "PC15_24") (pintype "passive"))
    )
    (net (code "265") (name "unconnected-(U14-VBAT-Pad21)") (class "Default")
      (node (ref "U14") (pin "21") (pinfunction "VBAT_21") (pintype "passive"))
    )
  )
)
